# homeboard29.net
KiCad netlist of a schematic drawn in EAGLE
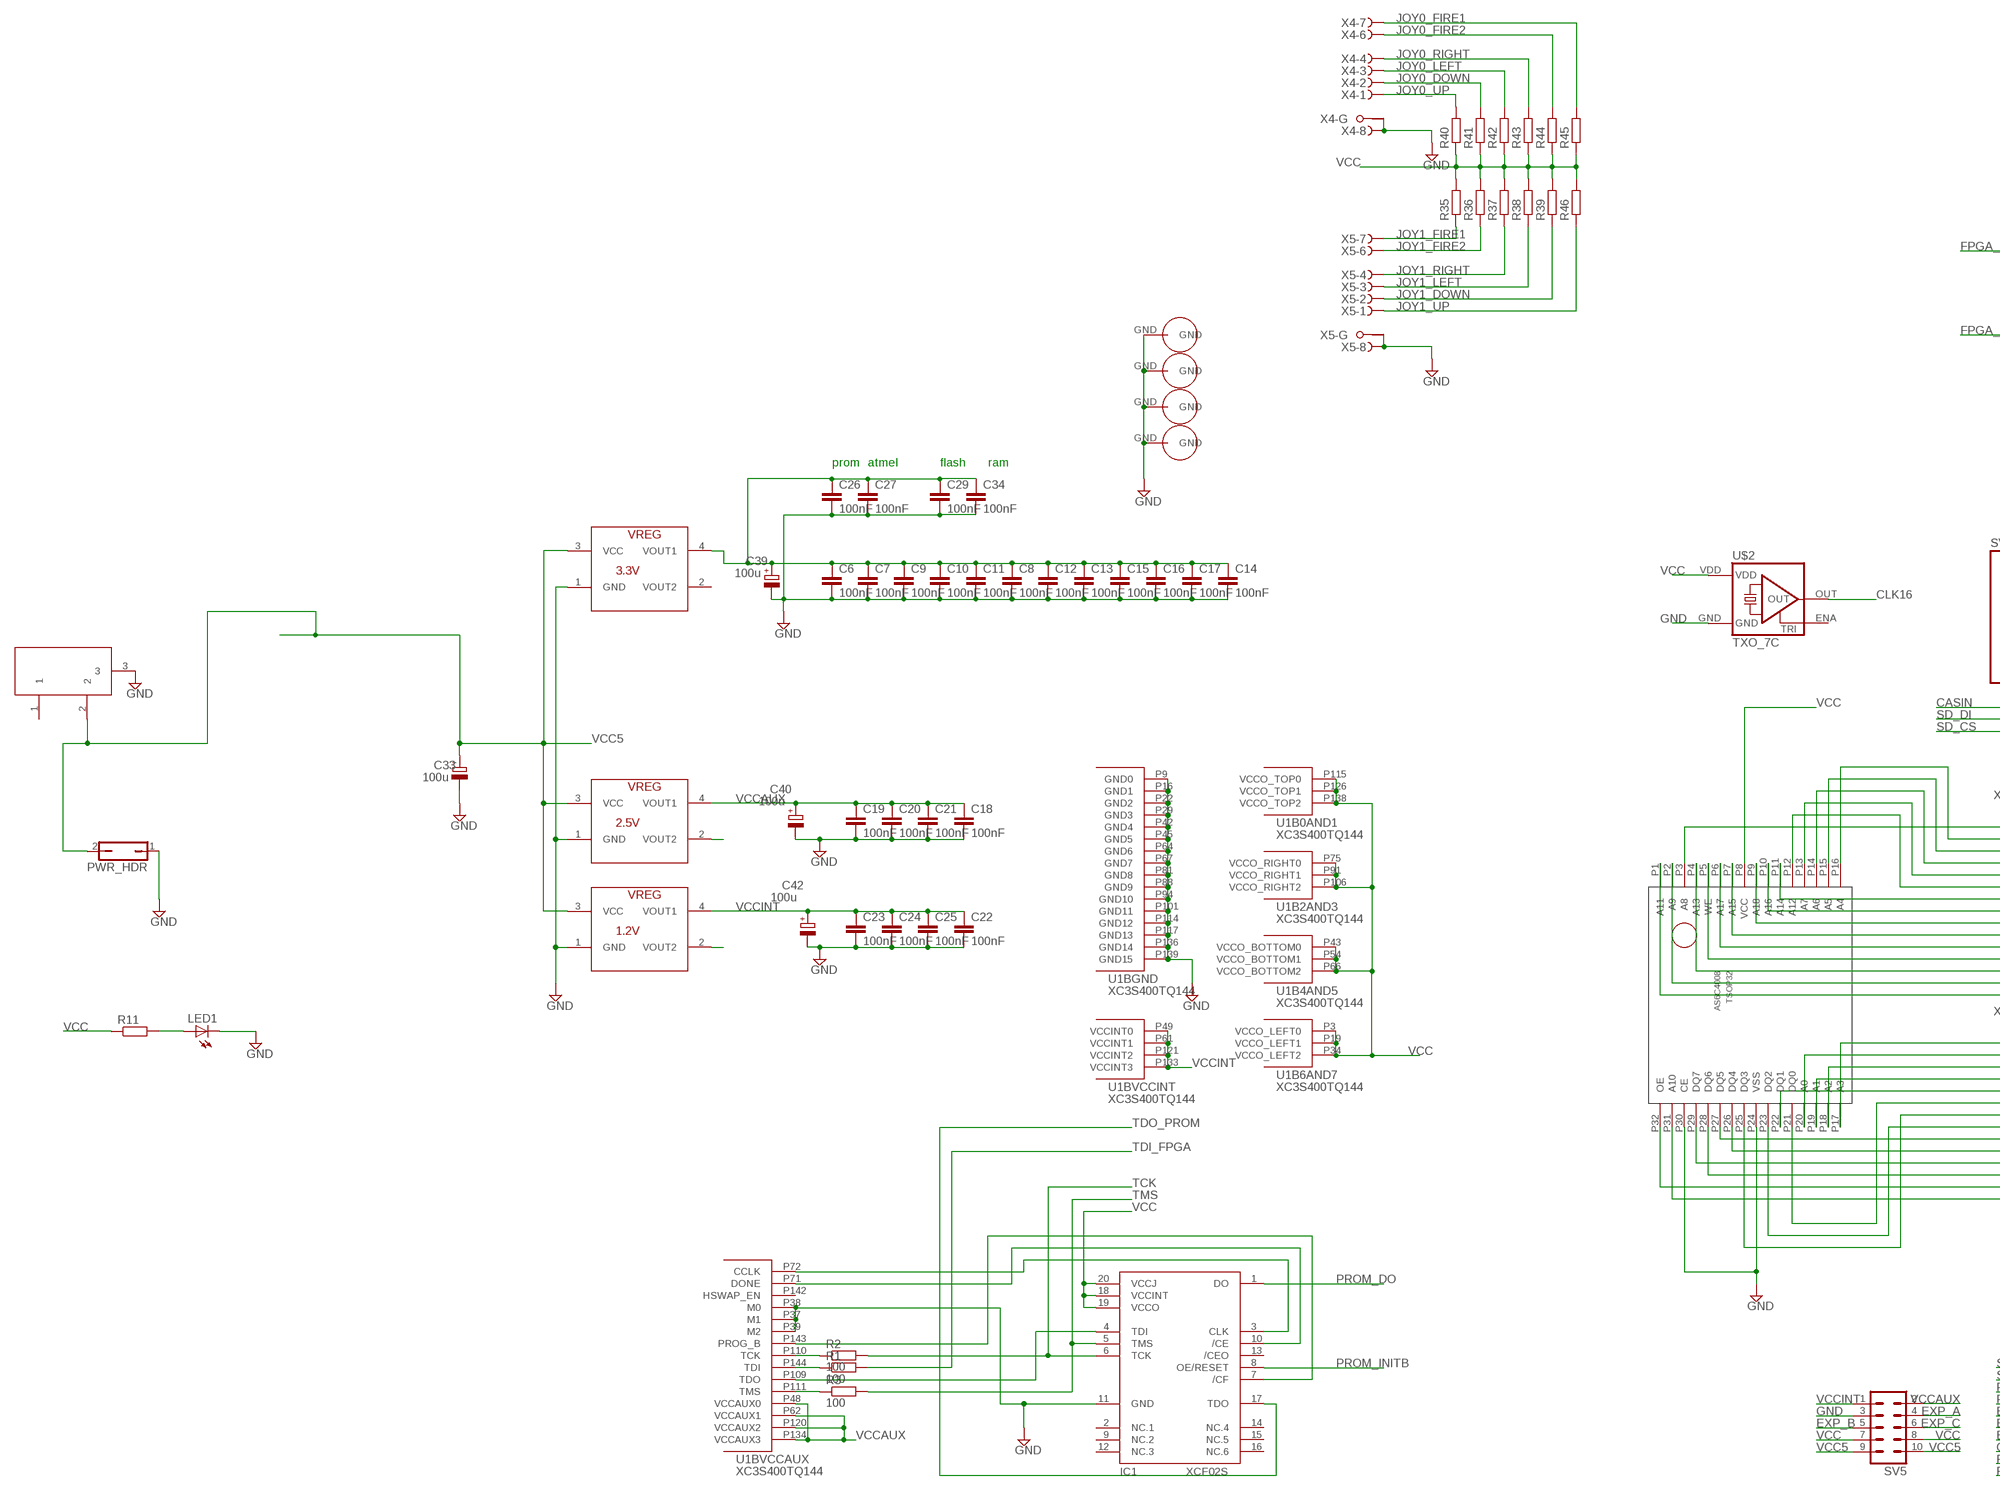
[diagram p0: schematic, sheet 1, part 1 of 3]
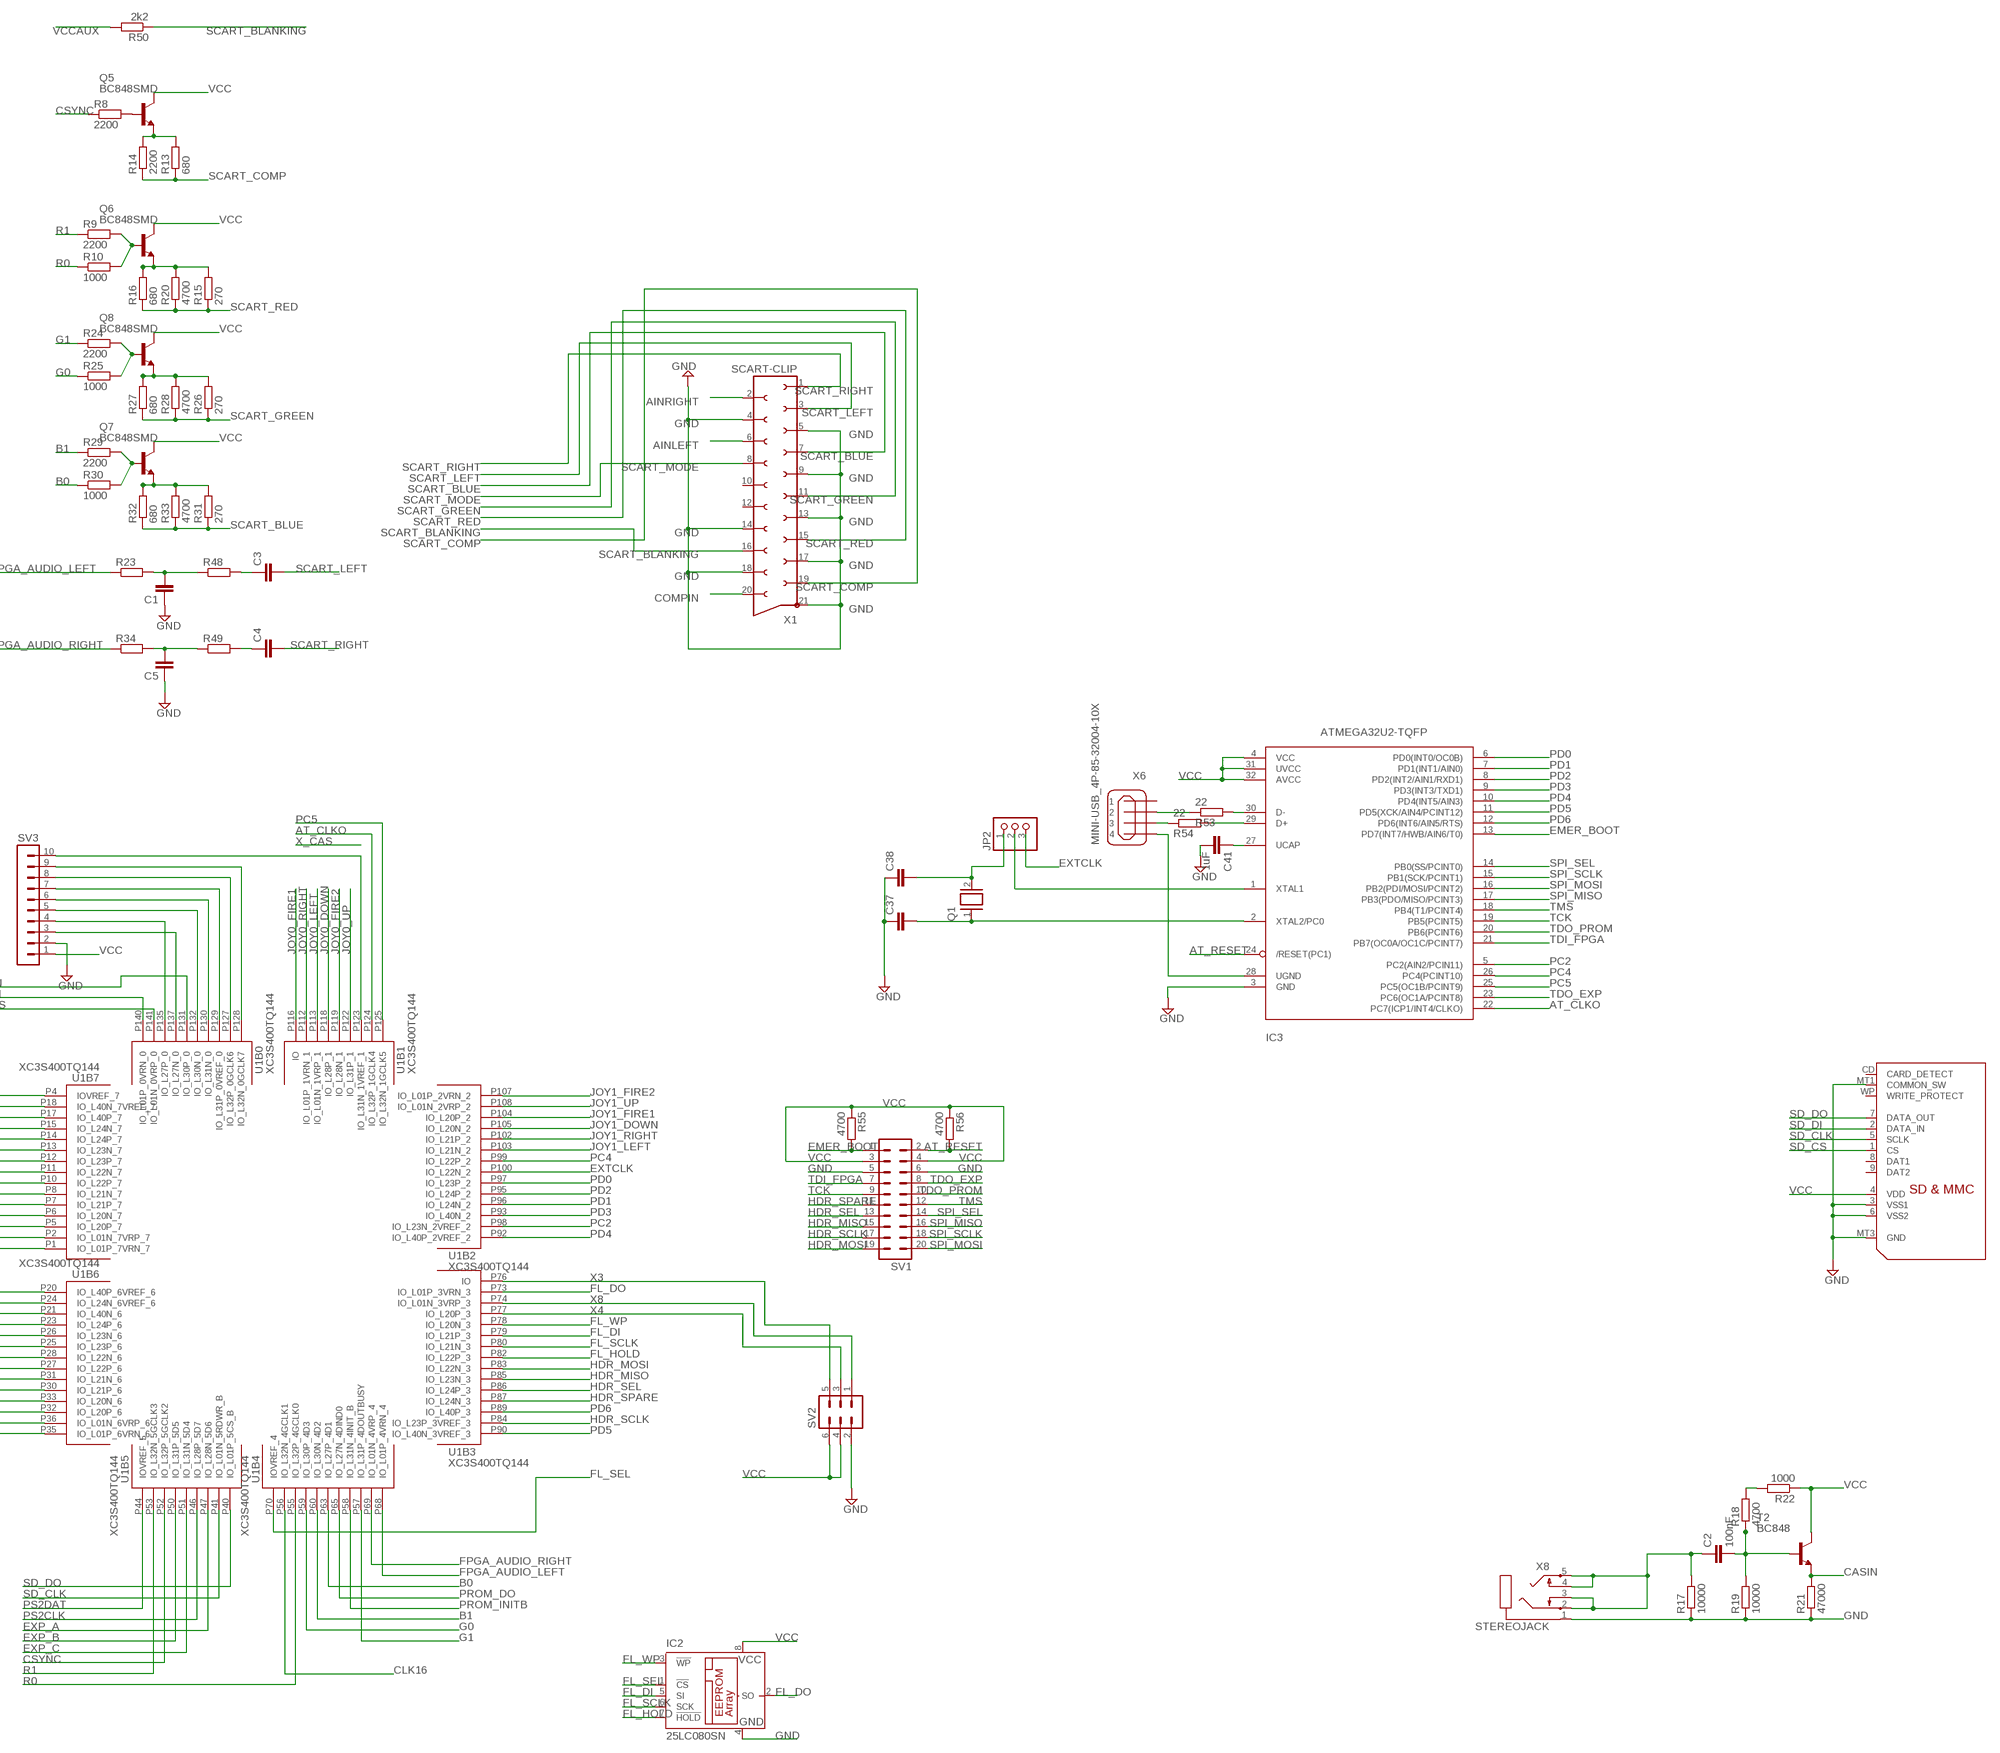
[diagram p1: schematic, sheet 1, part 2 of 3]
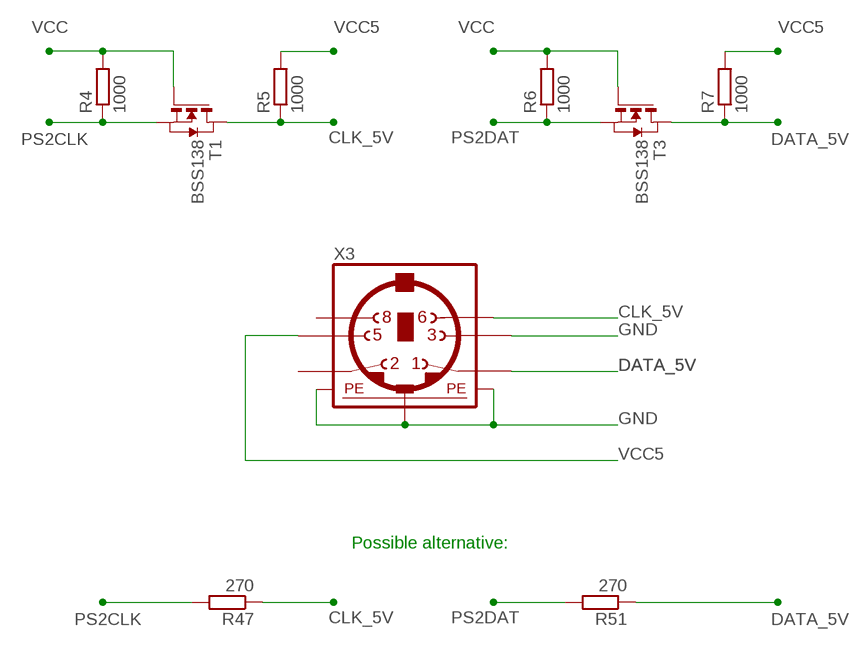
[diagram p2: schematic, sheet 1, part 3 of 3]

(export (version "E")
  (design (tool "Eeschema 10.0.6"))
  (components
    (comp (ref "C1")
      (value "C-EUC0603")
      (footprint "eagle-import:C0603")
      (libsource (lib "eagle-import") (part "resistor_C-EUC0603"))
    )
    (comp (ref "C2")
      (value "100nF")
      (footprint "eagle-import:C0603")
      (libsource (lib "eagle-import") (part "resistor_C-EUC0603"))
    )
    (comp (ref "C3")
      (value "C-EUC0603")
      (footprint "eagle-import:C0603")
      (libsource (lib "eagle-import") (part "resistor_C-EUC0603"))
    )
    (comp (ref "C4")
      (value "C-EUC0603")
      (footprint "eagle-import:C0603")
      (libsource (lib "eagle-import") (part "resistor_C-EUC0603"))
    )
    (comp (ref "C5")
      (value "C-EUC0603")
      (footprint "eagle-import:C0603")
      (libsource (lib "eagle-import") (part "resistor_C-EUC0603"))
    )
    (comp (ref "C6")
      (value "100nF")
      (footprint "eagle-import:C0603")
      (libsource (lib "eagle-import") (part "C-EUC0603"))
    )
    (comp (ref "C7")
      (value "100nF")
      (footprint "eagle-import:C0603")
      (libsource (lib "eagle-import") (part "C-EUC0603"))
    )
    (comp (ref "C8")
      (value "100nF")
      (footprint "eagle-import:C0603")
      (libsource (lib "eagle-import") (part "C-EUC0603"))
    )
    (comp (ref "C9")
      (value "100nF")
      (footprint "eagle-import:C0603")
      (libsource (lib "eagle-import") (part "C-EUC0603"))
    )
    (comp (ref "C10")
      (value "100nF")
      (footprint "eagle-import:C0603")
      (libsource (lib "eagle-import") (part "C-EUC0603"))
    )
    (comp (ref "C11")
      (value "100nF")
      (footprint "eagle-import:C0603")
      (libsource (lib "eagle-import") (part "C-EUC0603"))
    )
    (comp (ref "C12")
      (value "100nF")
      (footprint "eagle-import:C0603")
      (libsource (lib "eagle-import") (part "C-EUC0603"))
    )
    (comp (ref "C13")
      (value "100nF")
      (footprint "eagle-import:C0603")
      (libsource (lib "eagle-import") (part "C-EUC0603"))
    )
    (comp (ref "C14")
      (value "100nF")
      (footprint "eagle-import:C0603")
      (libsource (lib "eagle-import") (part "C-EUC0603"))
    )
    (comp (ref "C15")
      (value "100nF")
      (footprint "eagle-import:C0603")
      (libsource (lib "eagle-import") (part "C-EUC0603"))
    )
    (comp (ref "C16")
      (value "100nF")
      (footprint "eagle-import:C0603")
      (libsource (lib "eagle-import") (part "C-EUC0603"))
    )
    (comp (ref "C17")
      (value "100nF")
      (footprint "eagle-import:C0603")
      (libsource (lib "eagle-import") (part "C-EUC0603"))
    )
    (comp (ref "C18")
      (value "100nF")
      (footprint "eagle-import:C0603")
      (libsource (lib "eagle-import") (part "C-EUC0603"))
    )
    (comp (ref "C19")
      (value "100nF")
      (footprint "eagle-import:C0603")
      (libsource (lib "eagle-import") (part "C-EUC0603"))
    )
    (comp (ref "C20")
      (value "100nF")
      (footprint "eagle-import:C0603")
      (libsource (lib "eagle-import") (part "C-EUC0603"))
    )
    (comp (ref "C21")
      (value "100nF")
      (footprint "eagle-import:C0603")
      (libsource (lib "eagle-import") (part "C-EUC0603"))
    )
    (comp (ref "C22")
      (value "100nF")
      (footprint "eagle-import:C0603")
      (libsource (lib "eagle-import") (part "C-EUC0603"))
    )
    (comp (ref "C23")
      (value "100nF")
      (footprint "eagle-import:C0603")
      (libsource (lib "eagle-import") (part "C-EUC0603"))
    )
    (comp (ref "C24")
      (value "100nF")
      (footprint "eagle-import:C0603")
      (libsource (lib "eagle-import") (part "C-EUC0603"))
    )
    (comp (ref "C25")
      (value "100nF")
      (footprint "eagle-import:C0603")
      (libsource (lib "eagle-import") (part "C-EUC0603"))
    )
    (comp (ref "C26")
      (value "100nF")
      (footprint "eagle-import:C0603")
      (libsource (lib "eagle-import") (part "C-EUC0603"))
    )
    (comp (ref "C27")
      (value "100nF")
      (footprint "eagle-import:C0603")
      (libsource (lib "eagle-import") (part "C-EUC0603"))
    )
    (comp (ref "C29")
      (value "100nF")
      (footprint "eagle-import:C0603")
      (libsource (lib "eagle-import") (part "C-EUC0603"))
    )
    (comp (ref "C33")
      (value "100u")
      (footprint "eagle-import:PANASONIC_D")
      (libsource (lib "eagle-import") (part "CPOL-EUD"))
    )
    (comp (ref "C34")
      (value "100nF")
      (footprint "eagle-import:C0603")
      (libsource (lib "eagle-import") (part "C-EUC0603"))
    )
    (comp (ref "C37")
      (value "C-EUC0805")
      (footprint "eagle-import:C0805")
      (libsource (lib "eagle-import") (part "C-EUC0805"))
    )
    (comp (ref "C38")
      (value "C-EUC0805")
      (footprint "eagle-import:C0805")
      (libsource (lib "eagle-import") (part "C-EUC0805"))
    )
    (comp (ref "C39")
      (value "100u")
      (footprint "eagle-import:PANASONIC_D")
      (libsource (lib "eagle-import") (part "CPOL-EUD"))
    )
    (comp (ref "C40")
      (value "100u")
      (footprint "eagle-import:PANASONIC_D")
      (libsource (lib "eagle-import") (part "CPOL-EUD"))
    )
    (comp (ref "C41")
      (value "1uF")
      (footprint "eagle-import:C0805")
      (libsource (lib "eagle-import") (part "C-EUC0805"))
    )
    (comp (ref "C42")
      (value "100u")
      (footprint "eagle-import:PANASONIC_D")
      (libsource (lib "eagle-import") (part "CPOL-EUD"))
    )
    (comp (ref "IC1")
      (value "XCF02S")
      (footprint "eagle-import:VO20")
      (libsource (lib "eagle-import") (part "XCF02S"))
    )
    (comp (ref "IC2")
      (value "25LC080SN")
      (footprint "eagle-import:SO-08")
      (fields (field (name "MF") "MICROCHIP") (field (name "MPN") "25LC080/SN"))
      (libsource (lib "eagle-import") (part "25SNLC080"))
    )
    (comp (ref "IC3")
      (value "ATMEGA32U2-TQFP")
      (footprint "eagle-import:TQFP32-08")
      (libsource (lib "eagle-import") (part "ATMEGA32U2-TQFP"))
    )
    (comp (ref "JP2")
      (value "PINHD-1X3")
      (footprint "eagle-import:1X03")
      (libsource (lib "eagle-import") (part "PINHD-1X3"))
    )
    (comp (ref "LED1")
      (value "LEDCHIPLED_0805")
      (footprint "eagle-import:CHIPLED_0805")
      (libsource (lib "eagle-import") (part "LEDCHIPLED_0805"))
    )
    (comp (ref "PWR_HDR")
      (value "JP1Q")
      (footprint "eagle-import:JP1")
      (libsource (lib "eagle-import") (part "JP1Q"))
    )
    (comp (ref "Q1")
      (value "XTAL/S")
      (footprint "eagle-import:QS")
      (libsource (lib "eagle-import") (part "XTAL/S"))
    )
    (comp (ref "Q5")
      (value "BC848SMD")
      (footprint "eagle-import:SOT23")
      (libsource (lib "eagle-import") (part "BC848SMD"))
    )
    (comp (ref "Q6")
      (value "BC848SMD")
      (footprint "eagle-import:SOT23")
      (libsource (lib "eagle-import") (part "BC848SMD"))
    )
    (comp (ref "Q7")
      (value "BC848SMD")
      (footprint "eagle-import:SOT23")
      (libsource (lib "eagle-import") (part "BC848SMD"))
    )
    (comp (ref "Q8")
      (value "BC848SMD")
      (footprint "eagle-import:SOT23")
      (libsource (lib "eagle-import") (part "BC848SMD"))
    )
    (comp (ref "R1")
      (value "100")
      (footprint "eagle-import:R0805")
      (libsource (lib "eagle-import") (part "R-EU_R0805"))
    )
    (comp (ref "R2")
      (value "100")
      (footprint "eagle-import:R0805")
      (libsource (lib "eagle-import") (part "R-EU_R0805"))
    )
    (comp (ref "R3")
      (value "100")
      (footprint "eagle-import:R0805")
      (libsource (lib "eagle-import") (part "R-EU_R0805"))
    )
    (comp (ref "R4")
      (value "1000")
      (footprint "eagle-import:R0805")
      (libsource (lib "eagle-import") (part "R-EU_R0805"))
    )
    (comp (ref "R5")
      (value "1000")
      (footprint "eagle-import:R0805")
      (libsource (lib "eagle-import") (part "R-EU_R0805"))
    )
    (comp (ref "R6")
      (value "1000")
      (footprint "eagle-import:R0805")
      (libsource (lib "eagle-import") (part "R-EU_R0805"))
    )
    (comp (ref "R7")
      (value "1000")
      (footprint "eagle-import:R0805")
      (libsource (lib "eagle-import") (part "R-EU_R0805"))
    )
    (comp (ref "R8")
      (value "2200")
      (footprint "eagle-import:R0805")
      (libsource (lib "eagle-import") (part "R-EU_R0805"))
    )
    (comp (ref "R9")
      (value "2200")
      (footprint "eagle-import:R0805")
      (libsource (lib "eagle-import") (part "R-EU_R0805"))
    )
    (comp (ref "R10")
      (value "1000")
      (footprint "eagle-import:R0805")
      (libsource (lib "eagle-import") (part "R-EU_R0805"))
    )
    (comp (ref "R11")
      (value "R-EU_M0805")
      (footprint "eagle-import:M0805")
      (libsource (lib "eagle-import") (part "resistor_R-EU_M0805"))
    )
    (comp (ref "R13")
      (value "680")
      (footprint "eagle-import:R0805")
      (libsource (lib "eagle-import") (part "R-EU_R0805"))
    )
    (comp (ref "R14")
      (value "2200")
      (footprint "eagle-import:R0805")
      (libsource (lib "eagle-import") (part "R-EU_R0805"))
    )
    (comp (ref "R15")
      (value "270")
      (footprint "eagle-import:R0805")
      (libsource (lib "eagle-import") (part "R-EU_R0805"))
    )
    (comp (ref "R16")
      (value "680")
      (footprint "eagle-import:R0805")
      (libsource (lib "eagle-import") (part "R-EU_R0805"))
    )
    (comp (ref "R17")
      (value "10000")
      (footprint "eagle-import:R0805")
      (libsource (lib "eagle-import") (part "R-EU_R0805"))
    )
    (comp (ref "R18")
      (value "4700")
      (footprint "eagle-import:R0805")
      (libsource (lib "eagle-import") (part "R-EU_R0805"))
    )
    (comp (ref "R19")
      (value "10000")
      (footprint "eagle-import:R0805")
      (libsource (lib "eagle-import") (part "R-EU_R0805"))
    )
    (comp (ref "R20")
      (value "4700")
      (footprint "eagle-import:R0805")
      (libsource (lib "eagle-import") (part "R-EU_R0805"))
    )
    (comp (ref "R21")
      (value "47000")
      (footprint "eagle-import:R0805")
      (libsource (lib "eagle-import") (part "R-EU_R0805"))
    )
    (comp (ref "R22")
      (value "1000")
      (footprint "eagle-import:R0805")
      (libsource (lib "eagle-import") (part "R-EU_R0805"))
    )
    (comp (ref "R23")
      (value "R-EU_M0805")
      (footprint "eagle-import:M0805")
      (libsource (lib "eagle-import") (part "resistor_R-EU_M0805"))
    )
    (comp (ref "R24")
      (value "2200")
      (footprint "eagle-import:R0805")
      (libsource (lib "eagle-import") (part "R-EU_R0805"))
    )
    (comp (ref "R25")
      (value "1000")
      (footprint "eagle-import:R0805")
      (libsource (lib "eagle-import") (part "R-EU_R0805"))
    )
    (comp (ref "R26")
      (value "270")
      (footprint "eagle-import:R0805")
      (libsource (lib "eagle-import") (part "R-EU_R0805"))
    )
    (comp (ref "R27")
      (value "680")
      (footprint "eagle-import:R0805")
      (libsource (lib "eagle-import") (part "R-EU_R0805"))
    )
    (comp (ref "R28")
      (value "4700")
      (footprint "eagle-import:R0805")
      (libsource (lib "eagle-import") (part "R-EU_R0805"))
    )
    (comp (ref "R29")
      (value "2200")
      (footprint "eagle-import:R0805")
      (libsource (lib "eagle-import") (part "R-EU_R0805"))
    )
    (comp (ref "R30")
      (value "1000")
      (footprint "eagle-import:R0805")
      (libsource (lib "eagle-import") (part "R-EU_R0805"))
    )
    (comp (ref "R31")
      (value "270")
      (footprint "eagle-import:R0805")
      (libsource (lib "eagle-import") (part "R-EU_R0805"))
    )
    (comp (ref "R32")
      (value "680")
      (footprint "eagle-import:R0805")
      (libsource (lib "eagle-import") (part "R-EU_R0805"))
    )
    (comp (ref "R33")
      (value "4700")
      (footprint "eagle-import:R0805")
      (libsource (lib "eagle-import") (part "R-EU_R0805"))
    )
    (comp (ref "R34")
      (value "R-EU_M0805")
      (footprint "eagle-import:M0805")
      (libsource (lib "eagle-import") (part "resistor_R-EU_M0805"))
    )
    (comp (ref "R35")
      (value "R-EU_M0805")
      (footprint "eagle-import:M0805")
      (libsource (lib "eagle-import") (part "resistor_R-EU_M0805"))
    )
    (comp (ref "R36")
      (value "R-EU_M0805")
      (footprint "eagle-import:M0805")
      (libsource (lib "eagle-import") (part "resistor_R-EU_M0805"))
    )
    (comp (ref "R37")
      (value "R-EU_M0805")
      (footprint "eagle-import:M0805")
      (libsource (lib "eagle-import") (part "resistor_R-EU_M0805"))
    )
    (comp (ref "R38")
      (value "R-EU_M0805")
      (footprint "eagle-import:M0805")
      (libsource (lib "eagle-import") (part "resistor_R-EU_M0805"))
    )
    (comp (ref "R39")
      (value "R-EU_M0805")
      (footprint "eagle-import:M0805")
      (libsource (lib "eagle-import") (part "resistor_R-EU_M0805"))
    )
    (comp (ref "R40")
      (value "R-EU_M0805")
      (footprint "eagle-import:M0805")
      (libsource (lib "eagle-import") (part "resistor_R-EU_M0805"))
    )
    (comp (ref "R41")
      (value "R-EU_M0805")
      (footprint "eagle-import:M0805")
      (libsource (lib "eagle-import") (part "resistor_R-EU_M0805"))
    )
    (comp (ref "R42")
      (value "R-EU_M0805")
      (footprint "eagle-import:M0805")
      (libsource (lib "eagle-import") (part "resistor_R-EU_M0805"))
    )
    (comp (ref "R43")
      (value "R-EU_M0805")
      (footprint "eagle-import:M0805")
      (libsource (lib "eagle-import") (part "resistor_R-EU_M0805"))
    )
    (comp (ref "R44")
      (value "R-EU_M0805")
      (footprint "eagle-import:M0805")
      (libsource (lib "eagle-import") (part "resistor_R-EU_M0805"))
    )
    (comp (ref "R45")
      (value "R-EU_M0805")
      (footprint "eagle-import:M0805")
      (libsource (lib "eagle-import") (part "resistor_R-EU_M0805"))
    )
    (comp (ref "R46")
      (value "R-EU_M0805")
      (footprint "eagle-import:M0805")
      (libsource (lib "eagle-import") (part "resistor_R-EU_M0805"))
    )
    (comp (ref "R47")
      (value "270")
      (footprint "eagle-import:R0805")
      (libsource (lib "eagle-import") (part "R-EU_R0805"))
    )
    (comp (ref "R48")
      (value "R-EU_M0805")
      (footprint "eagle-import:M0805")
      (libsource (lib "eagle-import") (part "resistor_R-EU_M0805"))
    )
    (comp (ref "R49")
      (value "R-EU_M0805")
      (footprint "eagle-import:M0805")
      (libsource (lib "eagle-import") (part "resistor_R-EU_M0805"))
    )
    (comp (ref "R50")
      (value "2k2")
      (footprint "eagle-import:M0805")
      (libsource (lib "eagle-import") (part "resistor_R-EU_M0805"))
    )
    (comp (ref "R51")
      (value "270")
      (footprint "eagle-import:R0805")
      (libsource (lib "eagle-import") (part "R-EU_R0805"))
    )
    (comp (ref "R53")
      (value "22")
      (footprint "eagle-import:R0805")
      (libsource (lib "eagle-import") (part "R-EU_R0805"))
    )
    (comp (ref "R54")
      (value "22")
      (footprint "eagle-import:R0805")
      (libsource (lib "eagle-import") (part "R-EU_R0805"))
    )
    (comp (ref "R55")
      (value "4700")
      (footprint "eagle-import:R0805")
      (libsource (lib "eagle-import") (part "R-EU_R0805"))
    )
    (comp (ref "R56")
      (value "4700")
      (footprint "eagle-import:R0805")
      (libsource (lib "eagle-import") (part "R-EU_R0805"))
    )
    (comp (ref "REG1.2")
      (value "1.2V")
      (footprint "eagle-import:SOT223")
      (libsource (lib "eagle-import") (part "NX1117"))
    )
    (comp (ref "REG2.5")
      (value "2.5V")
      (footprint "eagle-import:SOT223")
      (libsource (lib "eagle-import") (part "NX1117"))
    )
    (comp (ref "SV1")
      (value "MA10-2")
      (footprint "eagle-import:MA10-2")
      (fields (field (name "OC_FARNELL") "unknown") (field (name "OC_NEWARK") "unknown"))
      (libsource (lib "eagle-import") (part "MA10-2"))
    )
    (comp (ref "SV2")
      (value "MA03-2")
      (footprint "eagle-import:MA03-2")
      (libsource (lib "eagle-import") (part "MA03-2"))
    )
    (comp (ref "SV3")
      (value "MA10-1")
      (footprint "eagle-import:MA10-1")
      (libsource (lib "eagle-import") (part "MA10-1"))
    )
    (comp (ref "SV5")
      (value "MA05-2")
      (footprint "eagle-import:MA05-2")
      (libsource (lib "eagle-import") (part "MA05-2"))
    )
    (comp (ref "T1")
      (value "BSS138")
      (footprint "eagle-import:SOT-23")
      (libsource (lib "eagle-import") (part "NMOSSOT23"))
    )
    (comp (ref "T2")
      (value "BC848")
      (footprint "eagle-import:SOT23")
      (libsource (lib "eagle-import") (part "BC848"))
    )
    (comp (ref "T3")
      (value "BSS138")
      (footprint "eagle-import:SOT-23")
      (libsource (lib "eagle-import") (part "NMOSSOT23"))
    )
    (comp (ref "U$1")
      (value "GNDHOLE")
      (footprint "eagle-import:GNDHOLE")
      (libsource (lib "eagle-import") (part "GNDHOLE"))
    )
    (comp (ref "U$2")
      (value "TXO_7C")
      (footprint "eagle-import:OSC_7C")
      (libsource (lib "eagle-import") (part "TXO_7C"))
    )
    (comp (ref "U$3")
      (value "SDMMCNOHOLE")
      (footprint "eagle-import:SDCARD-NOHOLE")
      (libsource (lib "eagle-import") (part "SDMMCNOHOLE"))
    )
    (comp (ref "U$4")
      (value "3.3V")
      (footprint "eagle-import:SOT223")
      (libsource (lib "eagle-import") (part "NX1117"))
    )
    (comp (ref "U$6")
      (value "AS6C4008")
      (footprint "eagle-import:TSOP32")
      (libsource (lib "eagle-import") (part "AS6C4008"))
    )
    (comp (ref "U$7")
      (value "GNDHOLE")
      (footprint "eagle-import:GNDHOLE")
      (libsource (lib "eagle-import") (part "GNDHOLE"))
    )
    (comp (ref "U$8")
      (value "GNDHOLE")
      (footprint "eagle-import:GNDHOLE")
      (libsource (lib "eagle-import") (part "GNDHOLE"))
    )
    (comp (ref "U$9")
      (value "GNDHOLE")
      (footprint "eagle-import:GNDHOLE")
      (libsource (lib "eagle-import") (part "GNDHOLE"))
    )
    (comp (ref "U1")
      (value "XC3S400TQ144")
      (footprint "eagle-import:TQ144")
      (libsource (lib "eagle-import") (part "XC3S400TQ144"))
    )
    (comp (ref "X1")
      (value "SCART-CLIP")
      (footprint "eagle-import:SCART-CLIP")
      (libsource (lib "eagle-import") (part "SCART-CLIP"))
    )
    (comp (ref "X3")
      (value "MINI_DIN_6")
      (footprint "eagle-import:M_DIN6")
      (libsource (lib "eagle-import") (part "MINI_DIN_6"))
    )
    (comp (ref "X4")
      (value "F09HPS")
      (footprint "eagle-import:F09HP")
      (libsource (lib "eagle-import") (part "F09HPS"))
    )
    (comp (ref "X5")
      (value "F09HPS")
      (footprint "eagle-import:F09HP")
      (libsource (lib "eagle-import") (part "F09HPS"))
    )
    (comp (ref "X6")
      (value "MINI-USB_4P-85-32004-10X")
      (footprint "eagle-import:85-32004-10X")
      (libsource (lib "eagle-import") (part "MINI-USB_4P-85-32004-10X"))
    )
    (comp (ref "X7")
      (value "DC21MMX")
      (footprint "eagle-import:DC-21MM")
      (libsource (lib "eagle-import") (part "DC21MMX"))
    )
    (comp (ref "X8")
      (value "STEREOJACK")
      (footprint "eagle-import:20-0137")
      (libsource (lib "eagle-import") (part "STEREOJACK"))
    )
  )
  (nets
    (net (code "1") (name "/1") (class "Default")
      (node (ref "X7") (pin "1") (pinfunction "1_1") (pintype "power_in"))
    )
    (net (code "2") (name "/AINLEFT") (class "Default")
      (node (ref "X1") (pin "6") (pinfunction "6_6") (pintype "passive"))
    )
    (net (code "3") (name "/AINRIGHT") (class "Default")
      (node (ref "X1") (pin "2") (pinfunction "2_2") (pintype "passive"))
    )
    (net (code "4") (name "/AT_CLKO") (class "Default")
      (node (ref "IC3") (pin "22") (pinfunction "PC7(ICP1/INT4/CLKO)_22") (pintype "bidirectional"))
      (node (ref "U1") (pin "P124") (pinfunction "IO_L32P_1GCLK4_P124") (pintype "bidirectional"))
    )
    (net (code "5") (name "/AT_RESET") (class "Default")
      (node (ref "IC3") (pin "24") (pinfunction "/RESET(PC1)_24") (pintype "bidirectional"))
      (node (ref "R56") (pin "2") (pinfunction "2_2") (pintype "passive"))
      (node (ref "SV1") (pin "2") (pinfunction "2_2") (pintype "passive"))
    )
    (net (code "6") (name "/B0") (class "Default")
      (node (ref "R30") (pin "1") (pinfunction "1_1") (pintype "passive"))
      (node (ref "U1") (pin "P63") (pinfunction "IO_L27P_4D1_P63") (pintype "bidirectional"))
    )
    (net (code "7") (name "/B1") (class "Default")
      (node (ref "R29") (pin "1") (pinfunction "1_1") (pintype "passive"))
      (node (ref "U1") (pin "P60") (pinfunction "IO_L30N_4D2_P60") (pintype "bidirectional"))
    )
    (net (code "8") (name "/CASIN") (class "Default")
      (node (ref "R21") (pin "2") (pinfunction "2_2") (pintype "passive"))
      (node (ref "T2") (pin "2") (pinfunction "E_2") (pintype "passive"))
      (node (ref "U1") (pin "P131") (pinfunction "IO_L30P_0_P131") (pintype "bidirectional"))
    )
    (net (code "9") (name "/CLK16") (class "Default")
      (node (ref "U$2") (pin "OUT") (pinfunction "OUT_OUT") (pintype "output"))
      (node (ref "U1") (pin "P56") (pinfunction "IO_L32N_4GCLK1_P56") (pintype "bidirectional"))
    )
    (net (code "10") (name "/CLK_5V") (class "Default")
      (node (ref "R47") (pin "1") (pinfunction "1_1") (pintype "passive"))
      (node (ref "R5") (pin "1") (pinfunction "1_1") (pintype "passive"))
      (node (ref "T1") (pin "1") (pinfunction "D_1") (pintype "passive"))
      (node (ref "X3") (pin "6") (pinfunction "6_6") (pintype "passive"))
    )
    (net (code "11") (name "/COMPIN") (class "Default")
      (node (ref "X1") (pin "20") (pinfunction "20_20") (pintype "passive"))
    )
    (net (code "12") (name "/CSYNC") (class "Default")
      (node (ref "R8") (pin "1") (pinfunction "1_1") (pintype "passive"))
      (node (ref "U1") (pin "P52") (pinfunction "IO_L32P_5GCLK2_P52") (pintype "bidirectional"))
    )
    (net (code "13") (name "/DATA_5V") (class "Default")
      (node (ref "R51") (pin "1") (pinfunction "1_1") (pintype "passive"))
      (node (ref "R7") (pin "1") (pinfunction "1_1") (pintype "passive"))
      (node (ref "T3") (pin "1") (pinfunction "D_1") (pintype "passive"))
      (node (ref "X3") (pin "1") (pinfunction "1_1") (pintype "passive"))
    )
    (net (code "14") (name "/EMER_BOOT") (class "Default")
      (node (ref "IC3") (pin "13") (pinfunction "PD7(INT7/HWB/AIN6/T0)_13") (pintype "bidirectional"))
      (node (ref "R55") (pin "2") (pinfunction "2_2") (pintype "passive"))
      (node (ref "SV1") (pin "1") (pinfunction "1_1") (pintype "passive"))
    )
    (net (code "15") (name "/EXP_A") (class "Default")
      (node (ref "SV5") (pin "4") (pinfunction "4_4") (pintype "passive"))
      (node (ref "U1") (pin "P47") (pinfunction "IO_L28N_5D6_P47") (pintype "bidirectional"))
    )
    (net (code "16") (name "/EXP_B") (class "Default")
      (node (ref "SV5") (pin "5") (pinfunction "5_5") (pintype "passive"))
      (node (ref "U1") (pin "P50") (pinfunction "IO_L31P_5D5_P50") (pintype "bidirectional"))
    )
    (net (code "17") (name "/EXP_C") (class "Default")
      (node (ref "SV5") (pin "6") (pinfunction "6_6") (pintype "passive"))
      (node (ref "U1") (pin "P51") (pinfunction "IO_L31N_5D4_P51") (pintype "bidirectional"))
    )
    (net (code "18") (name "/EXTCLK") (class "Default")
      (node (ref "JP2") (pin "3") (pinfunction "3_3") (pintype "passive"))
      (node (ref "U1") (pin "P100") (pinfunction "IO_L22N_2_P100") (pintype "bidirectional"))
    )
    (net (code "19") (name "/FL_DI") (class "Default")
      (node (ref "IC2") (pin "5") (pinfunction "SI_5") (pintype "input"))
      (node (ref "U1") (pin "P79") (pinfunction "IO_L21P_3_P79") (pintype "bidirectional"))
    )
    (net (code "20") (name "/FL_DO") (class "Default")
      (node (ref "IC2") (pin "2") (pinfunction "SO_2") (pintype "bidirectional"))
      (node (ref "U1") (pin "P73") (pinfunction "IO_L01P_3VRN_3_P73") (pintype "bidirectional"))
    )
    (net (code "21") (name "/FL_HOLD") (class "Default")
      (node (ref "IC2") (pin "7") (pinfunction "~{HOLD}_7") (pintype "input"))
      (node (ref "U1") (pin "P82") (pinfunction "IO_L22P_3_P82") (pintype "bidirectional"))
    )
    (net (code "22") (name "/FL_SCLK") (class "Default")
      (node (ref "IC2") (pin "6") (pinfunction "SCK_6") (pintype "input"))
      (node (ref "U1") (pin "P80") (pinfunction "IO_L21N_3_P80") (pintype "bidirectional"))
    )
    (net (code "23") (name "/FL_SEL") (class "Default")
      (node (ref "IC2") (pin "1") (pinfunction "~{CS}_1") (pintype "input"))
      (node (ref "U1") (pin "P70") (pinfunction "IOVREF_4_P70") (pintype "bidirectional"))
    )
    (net (code "24") (name "/FL_WP") (class "Default")
      (node (ref "IC2") (pin "3") (pinfunction "~{WP}_3") (pintype "input"))
      (node (ref "U1") (pin "P78") (pinfunction "IO_L20N_3_P78") (pintype "bidirectional"))
    )
    (net (code "25") (name "/FPGA_AUDIO_LEFT") (class "Default")
      (node (ref "R23") (pin "1") (pinfunction "1_1") (pintype "passive"))
      (node (ref "U1") (pin "P68") (pinfunction "IO_L01P_4VRN_4_P68") (pintype "bidirectional"))
    )
    (net (code "26") (name "/FPGA_AUDIO_RIGHT") (class "Default")
      (node (ref "R34") (pin "1") (pinfunction "1_1") (pintype "passive"))
      (node (ref "U1") (pin "P69") (pinfunction "IO_L01N_4VRP_4_P69") (pintype "bidirectional"))
    )
    (net (code "27") (name "/G0") (class "Default")
      (node (ref "R25") (pin "1") (pinfunction "1_1") (pintype "passive"))
      (node (ref "U1") (pin "P59") (pinfunction "IO_L30P_4D3_P59") (pintype "bidirectional"))
    )
    (net (code "28") (name "/G1") (class "Default")
      (node (ref "R24") (pin "1") (pinfunction "1_1") (pintype "passive"))
      (node (ref "U1") (pin "P57") (pinfunction "IO_L31P_4DOUTBUSY_P57") (pintype "bidirectional"))
    )
    (net (code "29") (name "/HDR_MISO") (class "Default")
      (node (ref "SV1") (pin "15") (pinfunction "15_15") (pintype "passive"))
      (node (ref "U1") (pin "P85") (pinfunction "IO_L23N_3_P85") (pintype "bidirectional"))
    )
    (net (code "30") (name "/HDR_MOSI") (class "Default")
      (node (ref "SV1") (pin "19") (pinfunction "19_19") (pintype "passive"))
      (node (ref "U1") (pin "P83") (pinfunction "IO_L22N_3_P83") (pintype "bidirectional"))
    )
    (net (code "31") (name "/HDR_SCLK") (class "Default")
      (node (ref "SV1") (pin "17") (pinfunction "17_17") (pintype "passive"))
      (node (ref "U1") (pin "P84") (pinfunction "IO_L23P_3VREF_3_P84") (pintype "bidirectional"))
    )
    (net (code "32") (name "/HDR_SEL") (class "Default")
      (node (ref "SV1") (pin "13") (pinfunction "13_13") (pintype "passive"))
      (node (ref "U1") (pin "P86") (pinfunction "IO_L24P_3_P86") (pintype "bidirectional"))
    )
    (net (code "33") (name "/HDR_SPARE") (class "Default")
      (node (ref "SV1") (pin "11") (pinfunction "11_11") (pintype "passive"))
      (node (ref "U1") (pin "P87") (pinfunction "IO_L24N_3_P87") (pintype "bidirectional"))
    )
    (net (code "34") (name "/JOY0_DOWN") (class "Default")
      (node (ref "R41") (pin "2") (pinfunction "2_2") (pintype "passive"))
      (node (ref "U1") (pin "P118") (pinfunction "IO_L28P_1_P118") (pintype "bidirectional"))
      (node (ref "X4") (pin "2") (pinfunction "F_2") (pintype "passive"))
    )
    (net (code "35") (name "/JOY0_FIRE1") (class "Default")
      (node (ref "R45") (pin "2") (pinfunction "2_2") (pintype "passive"))
      (node (ref "U1") (pin "P116") (pinfunction "IO_P116") (pintype "bidirectional"))
      (node (ref "X4") (pin "7") (pinfunction "F_7") (pintype "passive"))
    )
    (net (code "36") (name "/JOY0_FIRE2") (class "Default")
      (node (ref "R44") (pin "2") (pinfunction "2_2") (pintype "passive"))
      (node (ref "U1") (pin "P119") (pinfunction "IO_L28N_1_P119") (pintype "bidirectional"))
      (node (ref "X4") (pin "6") (pinfunction "F_6") (pintype "passive"))
    )
    (net (code "37") (name "/JOY0_LEFT") (class "Default")
      (node (ref "R42") (pin "2") (pinfunction "2_2") (pintype "passive"))
      (node (ref "U1") (pin "P113") (pinfunction "IO_L01N_1VRP_1_P113") (pintype "bidirectional"))
      (node (ref "X4") (pin "3") (pinfunction "F_3") (pintype "passive"))
    )
    (net (code "38") (name "/JOY0_RIGHT") (class "Default")
      (node (ref "R43") (pin "2") (pinfunction "2_2") (pintype "passive"))
      (node (ref "U1") (pin "P112") (pinfunction "IO_L01P_1VRN_1_P112") (pintype "bidirectional"))
      (node (ref "X4") (pin "4") (pinfunction "F_4") (pintype "passive"))
    )
    (net (code "39") (name "/JOY0_UP") (class "Default")
      (node (ref "R40") (pin "2") (pinfunction "2_2") (pintype "passive"))
      (node (ref "U1") (pin "P122") (pinfunction "IO_L31P_1_P122") (pintype "bidirectional"))
      (node (ref "X4") (pin "1") (pinfunction "F_1") (pintype "passive"))
    )
    (net (code "40") (name "/JOY1_DOWN") (class "Default")
      (node (ref "R39") (pin "1") (pinfunction "1_1") (pintype "passive"))
      (node (ref "U1") (pin "P105") (pinfunction "IO_L20N_2_P105") (pintype "bidirectional"))
      (node (ref "X5") (pin "2") (pinfunction "F_2") (pintype "passive"))
    )
    (net (code "41") (name "/JOY1_FIRE1") (class "Default")
      (node (ref "R35") (pin "1") (pinfunction "1_1") (pintype "passive"))
      (node (ref "U1") (pin "P104") (pinfunction "IO_L20P_2_P104") (pintype "bidirectional"))
      (node (ref "X5") (pin "7") (pinfunction "F_7") (pintype "passive"))
    )
    (net (code "42") (name "/JOY1_FIRE2") (class "Default")
      (node (ref "R36") (pin "1") (pinfunction "1_1") (pintype "passive"))
      (node (ref "U1") (pin "P107") (pinfunction "IO_L01P_2VRN_2_P107") (pintype "bidirectional"))
      (node (ref "X5") (pin "6") (pinfunction "F_6") (pintype "passive"))
    )
    (net (code "43") (name "/JOY1_LEFT") (class "Default")
      (node (ref "R38") (pin "1") (pinfunction "1_1") (pintype "passive"))
      (node (ref "U1") (pin "P103") (pinfunction "IO_L21N_2_P103") (pintype "bidirectional"))
      (node (ref "X5") (pin "3") (pinfunction "F_3") (pintype "passive"))
    )
    (net (code "44") (name "/JOY1_RIGHT") (class "Default")
      (node (ref "R37") (pin "1") (pinfunction "1_1") (pintype "passive"))
      (node (ref "U1") (pin "P102") (pinfunction "IO_L21P_2_P102") (pintype "bidirectional"))
      (node (ref "X5") (pin "4") (pinfunction "F_4") (pintype "passive"))
    )
    (net (code "45") (name "/JOY1_UP") (class "Default")
      (node (ref "R46") (pin "1") (pinfunction "1_1") (pintype "passive"))
      (node (ref "U1") (pin "P108") (pinfunction "IO_L01N_2VRP_2_P108") (pintype "bidirectional"))
      (node (ref "X5") (pin "1") (pinfunction "F_1") (pintype "passive"))
    )
    (net (code "46") (name "/PC2") (class "Default")
      (node (ref "IC3") (pin "5") (pinfunction "PC2(AIN2/PCIN11)_5") (pintype "bidirectional"))
      (node (ref "U1") (pin "P98") (pinfunction "IO_L23N_2VREF_2_P98") (pintype "bidirectional"))
    )
    (net (code "47") (name "/PC4") (class "Default")
      (node (ref "IC3") (pin "26") (pinfunction "PC4(PCINT10)_26") (pintype "bidirectional"))
      (node (ref "U1") (pin "P99") (pinfunction "IO_L22P_2_P99") (pintype "bidirectional"))
    )
    (net (code "48") (name "/PC5") (class "Default")
      (node (ref "IC3") (pin "25") (pinfunction "PC5(OC1B/PCINT9)_25") (pintype "bidirectional"))
      (node (ref "U1") (pin "P125") (pinfunction "IO_L32N_1GCLK5_P125") (pintype "bidirectional"))
    )
    (net (code "49") (name "/PD0") (class "Default")
      (node (ref "IC3") (pin "6") (pinfunction "PD0(INT0/OC0B)_6") (pintype "bidirectional"))
      (node (ref "U1") (pin "P97") (pinfunction "IO_L23P_2_P97") (pintype "bidirectional"))
    )
    (net (code "50") (name "/PD1") (class "Default")
      (node (ref "IC3") (pin "7") (pinfunction "PD1(INT1/AIN0)_7") (pintype "bidirectional"))
      (node (ref "U1") (pin "P96") (pinfunction "IO_L24N_2_P96") (pintype "bidirectional"))
    )
    (net (code "51") (name "/PD2") (class "Default")
      (node (ref "IC3") (pin "8") (pinfunction "PD2(INT2/AIN1/RXD1)_8") (pintype "bidirectional"))
      (node (ref "U1") (pin "P95") (pinfunction "IO_L24P_2_P95") (pintype "bidirectional"))
    )
    (net (code "52") (name "/PD3") (class "Default")
      (node (ref "IC3") (pin "9") (pinfunction "PD3(INT3/TXD1)_9") (pintype "bidirectional"))
      (node (ref "U1") (pin "P93") (pinfunction "IO_L40N_2_P93") (pintype "bidirectional"))
    )
    (net (code "53") (name "/PD4") (class "Default")
      (node (ref "IC3") (pin "10") (pinfunction "PD4(INT5/AIN3)_10") (pintype "bidirectional"))
      (node (ref "U1") (pin "P92") (pinfunction "IO_L40P_2VREF_2_P92") (pintype "bidirectional"))
    )
    (net (code "54") (name "/PD5") (class "Default")
      (node (ref "IC3") (pin "11") (pinfunction "PD5(XCK/AIN4/PCINT12)_11") (pintype "bidirectional"))
      (node (ref "U1") (pin "P90") (pinfunction "IO_L40N_3VREF_3_P90") (pintype "bidirectional"))
    )
    (net (code "55") (name "/PD6") (class "Default")
      (node (ref "IC3") (pin "12") (pinfunction "PD6(INT6/AIN5/RTS)_12") (pintype "bidirectional"))
      (node (ref "U1") (pin "P89") (pinfunction "IO_L40P_3_P89") (pintype "bidirectional"))
    )
    (net (code "56") (name "/PROM_DO") (class "Default")
      (node (ref "IC1") (pin "1") (pinfunction "DO_1") (pintype "bidirectional"))
      (node (ref "U1") (pin "P65") (pinfunction "IO_L27N_4DIND0_P65") (pintype "bidirectional"))
    )
    (net (code "57") (name "/PROM_INITB") (class "Default")
      (node (ref "IC1") (pin "8") (pinfunction "OE/RESET_8") (pintype "bidirectional"))
      (node (ref "U1") (pin "P58") (pinfunction "IO_L31N_4INIT_B_P58") (pintype "bidirectional"))
    )
    (net (code "58") (name "/PS2CLK") (class "Default")
      (node (ref "R4") (pin "1") (pinfunction "1_1") (pintype "passive"))
      (node (ref "R47") (pin "2") (pinfunction "2_2") (pintype "passive"))
      (node (ref "T1") (pin "2") (pinfunction "S_2") (pintype "passive"))
      (node (ref "U1") (pin "P46") (pinfunction "IO_L28P_5D7_P46") (pintype "bidirectional"))
    )
    (net (code "59") (name "/PS2DAT") (class "Default")
      (node (ref "R51") (pin "2") (pinfunction "2_2") (pintype "passive"))
      (node (ref "R6") (pin "1") (pinfunction "1_1") (pintype "passive"))
      (node (ref "T3") (pin "2") (pinfunction "S_2") (pintype "passive"))
      (node (ref "U1") (pin "P44") (pinfunction "IOVREF_5_P44") (pintype "bidirectional"))
    )
    (net (code "60") (name "/R0") (class "Default")
      (node (ref "R10") (pin "1") (pinfunction "1_1") (pintype "passive"))
      (node (ref "U1") (pin "P55") (pinfunction "IO_L32P_4GCLK0_P55") (pintype "bidirectional"))
    )
    (net (code "61") (name "/R1") (class "Default")
      (node (ref "R9") (pin "1") (pinfunction "1_1") (pintype "passive"))
      (node (ref "U1") (pin "P53") (pinfunction "IO_L32N_5GCLK3_P53") (pintype "bidirectional"))
    )
    (net (code "62") (name "/SCART_BLANKING") (class "Default")
      (node (ref "R50") (pin "1") (pinfunction "1_1") (pintype "passive"))
      (node (ref "X1") (pin "16") (pinfunction "16_16") (pintype "passive"))
    )
    (net (code "63") (name "/SCART_BLUE") (class "Default")
      (node (ref "R31") (pin "1") (pinfunction "1_1") (pintype "passive"))
      (node (ref "R32") (pin "1") (pinfunction "1_1") (pintype "passive"))
      (node (ref "R33") (pin "1") (pinfunction "1_1") (pintype "passive"))
      (node (ref "X1") (pin "7") (pinfunction "7_7") (pintype "passive"))
    )
    (net (code "64") (name "/SCART_COMP") (class "Default")
      (node (ref "R13") (pin "1") (pinfunction "1_1") (pintype "passive"))
      (node (ref "R14") (pin "1") (pinfunction "1_1") (pintype "passive"))
      (node (ref "X1") (pin "19") (pinfunction "19_19") (pintype "passive"))
    )
    (net (code "65") (name "/SCART_GREEN") (class "Default")
      (node (ref "R26") (pin "1") (pinfunction "1_1") (pintype "passive"))
      (node (ref "R27") (pin "1") (pinfunction "1_1") (pintype "passive"))
      (node (ref "R28") (pin "1") (pinfunction "1_1") (pintype "passive"))
      (node (ref "X1") (pin "11") (pinfunction "11_11") (pintype "passive"))
    )
    (net (code "66") (name "/SCART_LEFT") (class "Default")
      (node (ref "C3") (pin "2") (pinfunction "2_2") (pintype "passive"))
      (node (ref "X1") (pin "3") (pinfunction "3_3") (pintype "passive"))
    )
    (net (code "67") (name "/SCART_MODE") (class "Default")
      (node (ref "X1") (pin "8") (pinfunction "8_8") (pintype "passive"))
    )
    (net (code "68") (name "/SCART_RED") (class "Default")
      (node (ref "R15") (pin "1") (pinfunction "1_1") (pintype "passive"))
      (node (ref "R16") (pin "1") (pinfunction "1_1") (pintype "passive"))
      (node (ref "R20") (pin "1") (pinfunction "1_1") (pintype "passive"))
      (node (ref "X1") (pin "15") (pinfunction "15_15") (pintype "passive"))
    )
    (net (code "69") (name "/SCART_RIGHT") (class "Default")
      (node (ref "C4") (pin "2") (pinfunction "2_2") (pintype "passive"))
      (node (ref "X1") (pin "1") (pinfunction "1_1") (pintype "passive"))
    )
    (net (code "70") (name "/SD_CLK") (class "Default")
      (node (ref "U$3") (pin "5") (pinfunction "SCLK_5") (pintype "input"))
      (node (ref "U1") (pin "P41") (pinfunction "IO_L01N_5RDWR_B_P41") (pintype "bidirectional"))
    )
    (net (code "71") (name "/SD_CS") (class "Default")
      (node (ref "U$3") (pin "1") (pinfunction "CS_1") (pintype "input"))
      (node (ref "U1") (pin "P141") (pinfunction "IO_L01N_0VRP_0_P141") (pintype "bidirectional"))
    )
    (net (code "72") (name "/SD_DI") (class "Default")
      (node (ref "U$3") (pin "2") (pinfunction "DATA_IN_2") (pintype "input"))
      (node (ref "U1") (pin "P140") (pinfunction "IO_L01P_0VRN_0_P140") (pintype "bidirectional"))
    )
    (net (code "73") (name "/SD_DO") (class "Default")
      (node (ref "U$3") (pin "7") (pinfunction "DATA_OUT_7") (pintype "output"))
      (node (ref "U1") (pin "P40") (pinfunction "IO_L01P_5CS_B_P40") (pintype "bidirectional"))
    )
    (net (code "74") (name "/SPI_MISO") (class "Default")
      (node (ref "IC3") (pin "17") (pinfunction "PB3(PDO/MISO/PCINT3)_17") (pintype "bidirectional"))
      (node (ref "SV1") (pin "16") (pinfunction "16_16") (pintype "passive"))
    )
    (net (code "75") (name "/SPI_MOSI") (class "Default")
      (node (ref "IC3") (pin "16") (pinfunction "PB2(PDI/MOSI/PCINT2)_16") (pintype "bidirectional"))
      (node (ref "SV1") (pin "20") (pinfunction "20_20") (pintype "passive"))
    )
    (net (code "76") (name "/SPI_SCLK") (class "Default")
      (node (ref "IC3") (pin "15") (pinfunction "PB1(SCK/PCINT1)_15") (pintype "bidirectional"))
      (node (ref "SV1") (pin "18") (pinfunction "18_18") (pintype "passive"))
    )
    (net (code "77") (name "/SPI_SEL") (class "Default")
      (node (ref "IC3") (pin "14") (pinfunction "PB0(SS/PCINT0)_14") (pintype "bidirectional"))
      (node (ref "SV1") (pin "14") (pinfunction "14_14") (pintype "passive"))
    )
    (net (code "78") (name "/TCK") (class "Default")
      (node (ref "IC1") (pin "6") (pinfunction "TCK_6") (pintype "bidirectional"))
      (node (ref "IC3") (pin "19") (pinfunction "PB5(PCINT5)_19") (pintype "bidirectional"))
      (node (ref "R2") (pin "2") (pinfunction "2_2") (pintype "passive"))
      (node (ref "SV1") (pin "9") (pinfunction "9_9") (pintype "passive"))
    )
    (net (code "79") (name "/TDI_FPGA") (class "Default")
      (node (ref "IC3") (pin "21") (pinfunction "PB7(OC0A/OC1C/PCINT7)_21") (pintype "bidirectional"))
      (node (ref "R1") (pin "2") (pinfunction "2_2") (pintype "passive"))
      (node (ref "SV1") (pin "7") (pinfunction "7_7") (pintype "passive"))
    )
    (net (code "80") (name "/TDO_EXP") (class "Default")
      (node (ref "IC3") (pin "23") (pinfunction "PC6(OC1A/PCINT8)_23") (pintype "bidirectional"))
      (node (ref "SV1") (pin "8") (pinfunction "8_8") (pintype "passive"))
    )
    (net (code "81") (name "/TDO_PROM") (class "Default")
      (node (ref "IC1") (pin "17") (pinfunction "TDO_17") (pintype "bidirectional"))
      (node (ref "IC3") (pin "20") (pinfunction "PB6(PCINT6)_20") (pintype "bidirectional"))
      (node (ref "SV1") (pin "10") (pinfunction "10_10") (pintype "passive"))
    )
    (net (code "82") (name "/TMS") (class "Default")
      (node (ref "IC1") (pin "5") (pinfunction "TMS_5") (pintype "bidirectional"))
      (node (ref "IC3") (pin "18") (pinfunction "PB4(T1/PCINT4)_18") (pintype "bidirectional"))
      (node (ref "R3") (pin "2") (pinfunction "2_2") (pintype "passive"))
      (node (ref "SV1") (pin "12") (pinfunction "12_12") (pintype "passive"))
    )
    (net (code "83") (name "/VCC") (class "Default")
      (node (ref "C10") (pin "1") (pinfunction "1_1") (pintype "passive"))
      (node (ref "C11") (pin "1") (pinfunction "1_1") (pintype "passive"))
      (node (ref "C12") (pin "1") (pinfunction "1_1") (pintype "passive"))
      (node (ref "C13") (pin "1") (pinfunction "1_1") (pintype "passive"))
      (node (ref "C14") (pin "1") (pinfunction "1_1") (pintype "passive"))
      (node (ref "C15") (pin "1") (pinfunction "1_1") (pintype "passive"))
      (node (ref "C16") (pin "1") (pinfunction "1_1") (pintype "passive"))
      (node (ref "C17") (pin "1") (pinfunction "1_1") (pintype "passive"))
      (node (ref "C26") (pin "1") (pinfunction "1_1") (pintype "passive"))
      (node (ref "C27") (pin "1") (pinfunction "1_1") (pintype "passive"))
      (node (ref "C29") (pin "1") (pinfunction "1_1") (pintype "passive"))
      (node (ref "C34") (pin "1") (pinfunction "1_1") (pintype "passive"))
      (node (ref "C39") (pin "+") (pinfunction "+_+") (pintype "passive"))
      (node (ref "C6") (pin "1") (pinfunction "1_1") (pintype "passive"))
      (node (ref "C7") (pin "1") (pinfunction "1_1") (pintype "passive"))
      (node (ref "C8") (pin "1") (pinfunction "1_1") (pintype "passive"))
      (node (ref "C9") (pin "1") (pinfunction "1_1") (pintype "passive"))
      (node (ref "IC1") (pin "18") (pinfunction "VCCINT_18") (pintype "bidirectional"))
      (node (ref "IC1") (pin "19") (pinfunction "VCCO_19") (pintype "bidirectional"))
      (node (ref "IC1") (pin "20") (pinfunction "VCCJ_20") (pintype "bidirectional"))
      (node (ref "IC2") (pin "8") (pinfunction "VCC_8") (pintype "power_in"))
      (node (ref "IC3") (pin "31") (pinfunction "UVCC_31") (pintype "bidirectional"))
      (node (ref "IC3") (pin "32") (pinfunction "AVCC_32") (pintype "bidirectional"))
      (node (ref "IC3") (pin "4") (pinfunction "VCC_4") (pintype "bidirectional"))
      (node (ref "Q5") (pin "3") (pinfunction "C_3") (pintype "passive"))
      (node (ref "Q6") (pin "3") (pinfunction "C_3") (pintype "passive"))
      (node (ref "Q7") (pin "3") (pinfunction "C_3") (pintype "passive"))
      (node (ref "Q8") (pin "3") (pinfunction "C_3") (pintype "passive"))
      (node (ref "R11") (pin "1") (pinfunction "1_1") (pintype "passive"))
      (node (ref "R22") (pin "1") (pinfunction "1_1") (pintype "passive"))
      (node (ref "R35") (pin "2") (pinfunction "2_2") (pintype "passive"))
      (node (ref "R36") (pin "2") (pinfunction "2_2") (pintype "passive"))
      (node (ref "R37") (pin "2") (pinfunction "2_2") (pintype "passive"))
      (node (ref "R38") (pin "2") (pinfunction "2_2") (pintype "passive"))
      (node (ref "R39") (pin "2") (pinfunction "2_2") (pintype "passive"))
      (node (ref "R4") (pin "2") (pinfunction "2_2") (pintype "passive"))
      (node (ref "R40") (pin "1") (pinfunction "1_1") (pintype "passive"))
      (node (ref "R41") (pin "1") (pinfunction "1_1") (pintype "passive"))
      (node (ref "R42") (pin "1") (pinfunction "1_1") (pintype "passive"))
      (node (ref "R43") (pin "1") (pinfunction "1_1") (pintype "passive"))
      (node (ref "R44") (pin "1") (pinfunction "1_1") (pintype "passive"))
      (node (ref "R45") (pin "1") (pinfunction "1_1") (pintype "passive"))
      (node (ref "R46") (pin "2") (pinfunction "2_2") (pintype "passive"))
      (node (ref "R55") (pin "1") (pinfunction "1_1") (pintype "passive"))
      (node (ref "R56") (pin "1") (pinfunction "1_1") (pintype "passive"))
      (node (ref "R6") (pin "2") (pinfunction "2_2") (pintype "passive"))
      (node (ref "SV1") (pin "3") (pinfunction "3_3") (pintype "passive"))
      (node (ref "SV1") (pin "4") (pinfunction "4_4") (pintype "passive"))
      (node (ref "SV2") (pin "4") (pinfunction "4_4") (pintype "passive"))
      (node (ref "SV2") (pin "6") (pinfunction "6_6") (pintype "passive"))
      (node (ref "SV3") (pin "1") (pinfunction "1_1") (pintype "passive"))
      (node (ref "SV5") (pin "7") (pinfunction "7_7") (pintype "passive"))
      (node (ref "SV5") (pin "8") (pinfunction "8_8") (pintype "passive"))
      (node (ref "T1") (pin "3") (pinfunction "G_3") (pintype "passive"))
      (node (ref "T2") (pin "3") (pinfunction "C_3") (pintype "passive"))
      (node (ref "T3") (pin "3") (pinfunction "G_3") (pintype "passive"))
      (node (ref "U$2") (pin "VDD") (pinfunction "VDD_VDD") (pintype "power_in"))
      (node (ref "U$3") (pin "4") (pinfunction "VDD_4") (pintype "power_in"))
      (node (ref "U$4") (pin "4") (pinfunction "VOUT1_4") (pintype "bidirectional"))
      (node (ref "U$6") (pin "P8") (pinfunction "VCC_P8") (pintype "bidirectional"))
      (node (ref "U1") (pin "P106") (pinfunction "VCCO_RIGHT2_P106") (pintype "passive"))
      (node (ref "U1") (pin "P115") (pinfunction "VCCO_TOP0_P115") (pintype "passive"))
      (node (ref "U1") (pin "P126") (pinfunction "VCCO_TOP1_P126") (pintype "passive"))
      (node (ref "U1") (pin "P138") (pinfunction "VCCO_TOP2_P138") (pintype "passive"))
      (node (ref "U1") (pin "P19") (pinfunction "VCCO_LEFT1_P19") (pintype "passive"))
      (node (ref "U1") (pin "P3") (pinfunction "VCCO_LEFT0_P3") (pintype "passive"))
      (node (ref "U1") (pin "P34") (pinfunction "VCCO_LEFT2_P34") (pintype "passive"))
      (node (ref "U1") (pin "P43") (pinfunction "VCCO_BOTTOM0_P43") (pintype "passive"))
      (node (ref "U1") (pin "P54") (pinfunction "VCCO_BOTTOM1_P54") (pintype "passive"))
      (node (ref "U1") (pin "P66") (pinfunction "VCCO_BOTTOM2_P66") (pintype "passive"))
      (node (ref "U1") (pin "P75") (pinfunction "VCCO_RIGHT0_P75") (pintype "passive"))
      (node (ref "U1") (pin "P91") (pinfunction "VCCO_RIGHT1_P91") (pintype "passive"))
    )
    (net (code "84") (name "/VCC5") (class "Default")
      (node (ref "C33") (pin "+") (pinfunction "+_+") (pintype "passive"))
      (node (ref "PWR_HDR") (pin "2") (pinfunction "2_2") (pintype "passive"))
      (node (ref "R5") (pin "2") (pinfunction "2_2") (pintype "passive"))
      (node (ref "R7") (pin "2") (pinfunction "2_2") (pintype "passive"))
      (node (ref "REG1.2") (pin "3") (pinfunction "VCC_3") (pintype "bidirectional"))
      (node (ref "REG2.5") (pin "3") (pinfunction "VCC_3") (pintype "bidirectional"))
      (node (ref "SV5") (pin "10") (pinfunction "10_10") (pintype "passive"))
      (node (ref "SV5") (pin "9") (pinfunction "9_9") (pintype "passive"))
      (node (ref "U$4") (pin "3") (pinfunction "VCC_3") (pintype "bidirectional"))
      (node (ref "X3") (pin "5") (pinfunction "5_5") (pintype "passive"))
      (node (ref "X7") (pin "2") (pinfunction "2_2") (pintype "power_in"))
    )
    (net (code "85") (name "/VCCAUX") (class "Default")
      (node (ref "C18") (pin "1") (pinfunction "1_1") (pintype "passive"))
      (node (ref "C19") (pin "1") (pinfunction "1_1") (pintype "passive"))
      (node (ref "C20") (pin "1") (pinfunction "1_1") (pintype "passive"))
      (node (ref "C21") (pin "1") (pinfunction "1_1") (pintype "passive"))
      (node (ref "C40") (pin "+") (pinfunction "+_+") (pintype "passive"))
      (node (ref "R50") (pin "2") (pinfunction "2_2") (pintype "passive"))
      (node (ref "REG2.5") (pin "4") (pinfunction "VOUT1_4") (pintype "bidirectional"))
      (node (ref "SV5") (pin "2") (pinfunction "2_2") (pintype "passive"))
      (node (ref "U1") (pin "P120") (pinfunction "VCCAUX2_P120") (pintype "passive"))
      (node (ref "U1") (pin "P134") (pinfunction "VCCAUX3_P134") (pintype "passive"))
      (node (ref "U1") (pin "P48") (pinfunction "VCCAUX0_P48") (pintype "passive"))
      (node (ref "U1") (pin "P62") (pinfunction "VCCAUX1_P62") (pintype "passive"))
    )
    (net (code "86") (name "/VCCINT") (class "Default")
      (node (ref "C22") (pin "1") (pinfunction "1_1") (pintype "passive"))
      (node (ref "C23") (pin "1") (pinfunction "1_1") (pintype "passive"))
      (node (ref "C24") (pin "1") (pinfunction "1_1") (pintype "passive"))
      (node (ref "C25") (pin "1") (pinfunction "1_1") (pintype "passive"))
      (node (ref "C42") (pin "+") (pinfunction "+_+") (pintype "passive"))
      (node (ref "REG1.2") (pin "4") (pinfunction "VOUT1_4") (pintype "bidirectional"))
      (node (ref "SV5") (pin "1") (pinfunction "1_1") (pintype "passive"))
      (node (ref "U1") (pin "P121") (pinfunction "VCCINT2_P121") (pintype "passive"))
      (node (ref "U1") (pin "P133") (pinfunction "VCCINT3_P133") (pintype "passive"))
      (node (ref "U1") (pin "P49") (pinfunction "VCCINT0_P49") (pintype "passive"))
      (node (ref "U1") (pin "P61") (pinfunction "VCCINT1_P61") (pintype "passive"))
    )
    (net (code "87") (name "/X3") (class "Default")
      (node (ref "SV2") (pin "5") (pinfunction "5_5") (pintype "passive"))
      (node (ref "U1") (pin "P76") (pinfunction "IO_P76") (pintype "bidirectional"))
    )
    (net (code "88") (name "/X4") (class "Default")
      (node (ref "SV2") (pin "3") (pinfunction "3_3") (pintype "passive"))
      (node (ref "U1") (pin "P77") (pinfunction "IO_L20P_3_P77") (pintype "bidirectional"))
    )
    (net (code "89") (name "/X8") (class "Default")
      (node (ref "SV2") (pin "1") (pinfunction "1_1") (pintype "passive"))
      (node (ref "U1") (pin "P74") (pinfunction "IO_L01N_3VRP_3_P74") (pintype "bidirectional"))
    )
    (net (code "91") (name "GND") (class "Default")
      (node (ref "C1") (pin "1") (pinfunction "1_1") (pintype "passive"))
      (node (ref "C10") (pin "2") (pinfunction "2_2") (pintype "passive"))
      (node (ref "C11") (pin "2") (pinfunction "2_2") (pintype "passive"))
      (node (ref "C12") (pin "2") (pinfunction "2_2") (pintype "passive"))
      (node (ref "C13") (pin "2") (pinfunction "2_2") (pintype "passive"))
      (node (ref "C14") (pin "2") (pinfunction "2_2") (pintype "passive"))
      (node (ref "C15") (pin "2") (pinfunction "2_2") (pintype "passive"))
      (node (ref "C16") (pin "2") (pinfunction "2_2") (pintype "passive"))
      (node (ref "C17") (pin "2") (pinfunction "2_2") (pintype "passive"))
      (node (ref "C18") (pin "2") (pinfunction "2_2") (pintype "passive"))
      (node (ref "C19") (pin "2") (pinfunction "2_2") (pintype "passive"))
      (node (ref "C20") (pin "2") (pinfunction "2_2") (pintype "passive"))
      (node (ref "C21") (pin "2") (pinfunction "2_2") (pintype "passive"))
      (node (ref "C22") (pin "2") (pinfunction "2_2") (pintype "passive"))
      (node (ref "C23") (pin "2") (pinfunction "2_2") (pintype "passive"))
      (node (ref "C24") (pin "2") (pinfunction "2_2") (pintype "passive"))
      (node (ref "C25") (pin "2") (pinfunction "2_2") (pintype "passive"))
      (node (ref "C26") (pin "2") (pinfunction "2_2") (pintype "passive"))
      (node (ref "C27") (pin "2") (pinfunction "2_2") (pintype "passive"))
      (node (ref "C29") (pin "2") (pinfunction "2_2") (pintype "passive"))
      (node (ref "C33") (pin "-") (pinfunction "-_-") (pintype "passive"))
      (node (ref "C34") (pin "2") (pinfunction "2_2") (pintype "passive"))
      (node (ref "C37") (pin "1") (pinfunction "1_1") (pintype "passive"))
      (node (ref "C38") (pin "1") (pinfunction "1_1") (pintype "passive"))
      (node (ref "C39") (pin "-") (pinfunction "-_-") (pintype "passive"))
      (node (ref "C40") (pin "-") (pinfunction "-_-") (pintype "passive"))
      (node (ref "C41") (pin "2") (pinfunction "2_2") (pintype "passive"))
      (node (ref "C42") (pin "-") (pinfunction "-_-") (pintype "passive"))
      (node (ref "C5") (pin "1") (pinfunction "1_1") (pintype "passive"))
      (node (ref "C6") (pin "2") (pinfunction "2_2") (pintype "passive"))
      (node (ref "C7") (pin "2") (pinfunction "2_2") (pintype "passive"))
      (node (ref "C8") (pin "2") (pinfunction "2_2") (pintype "passive"))
      (node (ref "C9") (pin "2") (pinfunction "2_2") (pintype "passive"))
      (node (ref "IC1") (pin "11") (pinfunction "GND_11") (pintype "bidirectional"))
      (node (ref "IC2") (pin "4") (pinfunction "GND_4") (pintype "power_in"))
      (node (ref "IC3") (pin "3") (pinfunction "GND_3") (pintype "bidirectional"))
      (node (ref "LED1") (pin "C") (pinfunction "C_C") (pintype "passive"))
      (node (ref "PWR_HDR") (pin "1") (pinfunction "1_1") (pintype "passive"))
      (node (ref "R17") (pin "1") (pinfunction "1_1") (pintype "passive"))
      (node (ref "R19") (pin "1") (pinfunction "1_1") (pintype "passive"))
      (node (ref "R21") (pin "1") (pinfunction "1_1") (pintype "passive"))
      (node (ref "REG1.2") (pin "1") (pinfunction "GND_1") (pintype "bidirectional"))
      (node (ref "REG2.5") (pin "1") (pinfunction "GND_1") (pintype "bidirectional"))
      (node (ref "SV1") (pin "5") (pinfunction "5_5") (pintype "passive"))
      (node (ref "SV1") (pin "6") (pinfunction "6_6") (pintype "passive"))
      (node (ref "SV2") (pin "2") (pinfunction "2_2") (pintype "passive"))
      (node (ref "SV3") (pin "2") (pinfunction "2_2") (pintype "passive"))
      (node (ref "SV5") (pin "3") (pinfunction "3_3") (pintype "passive"))
      (node (ref "U$1") (pin "GND") (pinfunction "GND_GND") (pintype "bidirectional"))
      (node (ref "U$2") (pin "GND") (pinfunction "GND_GND") (pintype "power_in"))
      (node (ref "U$3") (pin "3") (pinfunction "VSS1_3") (pintype "power_in"))
      (node (ref "U$3") (pin "6") (pinfunction "VSS2_6") (pintype "power_in"))
      (node (ref "U$3") (pin "MT1") (pinfunction "COMMON_SW_MT1") (pintype "passive"))
      (node (ref "U$3") (pin "MT3") (pinfunction "GND_MT3") (pintype "power_in"))
      (node (ref "U$4") (pin "1") (pinfunction "GND_1") (pintype "bidirectional"))
      (node (ref "U$6") (pin "P24") (pinfunction "VSS_P24") (pintype "bidirectional"))
      (node (ref "U$6") (pin "P30") (pinfunction "CE_P30") (pintype "bidirectional"))
      (node (ref "U$7") (pin "GND") (pinfunction "GND_GND") (pintype "bidirectional"))
      (node (ref "U$8") (pin "GND") (pinfunction "GND_GND") (pintype "bidirectional"))
      (node (ref "U$9") (pin "GND") (pinfunction "GND_GND") (pintype "bidirectional"))
      (node (ref "U1") (pin "P101") (pinfunction "GND11_P101") (pintype "passive"))
      (node (ref "U1") (pin "P114") (pinfunction "GND12_P114") (pintype "passive"))
      (node (ref "U1") (pin "P117") (pinfunction "GND13_P117") (pintype "passive"))
      (node (ref "U1") (pin "P136") (pinfunction "GND14_P136") (pintype "passive"))
      (node (ref "U1") (pin "P139") (pinfunction "GND15_P139") (pintype "passive"))
      (node (ref "U1") (pin "P16") (pinfunction "GND1_P16") (pintype "passive"))
      (node (ref "U1") (pin "P22") (pinfunction "GND2_P22") (pintype "passive"))
      (node (ref "U1") (pin "P29") (pinfunction "GND3_P29") (pintype "passive"))
      (node (ref "U1") (pin "P37") (pinfunction "M1_P37") (pintype "bidirectional"))
      (node (ref "U1") (pin "P38") (pinfunction "M0_P38") (pintype "bidirectional"))
      (node (ref "U1") (pin "P39") (pinfunction "M2_P39") (pintype "bidirectional"))
      (node (ref "U1") (pin "P42") (pinfunction "GND4_P42") (pintype "passive"))
      (node (ref "U1") (pin "P45") (pinfunction "GND5_P45") (pintype "passive"))
      (node (ref "U1") (pin "P64") (pinfunction "GND6_P64") (pintype "passive"))
      (node (ref "U1") (pin "P67") (pinfunction "GND7_P67") (pintype "passive"))
      (node (ref "U1") (pin "P81") (pinfunction "GND8_P81") (pintype "passive"))
      (node (ref "U1") (pin "P88") (pinfunction "GND9_P88") (pintype "passive"))
      (node (ref "U1") (pin "P9") (pinfunction "GND0_P9") (pintype "passive"))
      (node (ref "U1") (pin "P94") (pinfunction "GND10_P94") (pintype "passive"))
      (node (ref "X1") (pin "13") (pinfunction "13_13") (pintype "passive"))
      (node (ref "X1") (pin "14") (pinfunction "14_14") (pintype "passive"))
      (node (ref "X1") (pin "17") (pinfunction "17_17") (pintype "passive"))
      (node (ref "X1") (pin "18") (pinfunction "18_18") (pintype "passive"))
      (node (ref "X1") (pin "21") (pinfunction "21_21") (pintype "passive"))
      (node (ref "X1") (pin "4") (pinfunction "4_4") (pintype "passive"))
      (node (ref "X1") (pin "5") (pinfunction "5_5") (pintype "passive"))
      (node (ref "X1") (pin "9") (pinfunction "9_9") (pintype "passive"))
      (node (ref "X3") (pin "3") (pinfunction "3_3") (pintype "passive"))
      (node (ref "X3") (pin "SH1") (pinfunction "PE1_SH1") (pintype "power_in"))
      (node (ref "X3") (pin "SH2") (pinfunction "PE2_SH2") (pintype "power_in"))
      (node (ref "X3") (pin "SH3") (pinfunction "PE3_SH3") (pintype "power_in"))
      (node (ref "X4") (pin "8") (pinfunction "F_8") (pintype "passive"))
      (node (ref "X4") (pin "G1") (pinfunction "G1_G1") (pintype "passive"))
      (node (ref "X5") (pin "8") (pinfunction "F_8") (pintype "passive"))
      (node (ref "X5") (pin "G1") (pinfunction "G1_G1") (pintype "passive"))
      (node (ref "X7") (pin "3") (pinfunction "3_3") (pintype "power_in"))
      (node (ref "X8") (pin "1") (pinfunction "1_1") (pintype "passive"))
    )
    (net (code "92") (name "Net-(C1-Pad2)") (class "Default")
      (node (ref "C1") (pin "2") (pinfunction "2_2") (pintype "passive"))
      (node (ref "R23") (pin "2") (pinfunction "2_2") (pintype "passive"))
      (node (ref "R48") (pin "1") (pinfunction "1_1") (pintype "passive"))
    )
    (net (code "93") (name "Net-(C2-Pad1)") (class "Default")
      (node (ref "C2") (pin "1") (pinfunction "1_1") (pintype "passive"))
      (node (ref "R17") (pin "2") (pinfunction "2_2") (pintype "passive"))
      (node (ref "X8") (pin "2") (pinfunction "2_2") (pintype "passive"))
      (node (ref "X8") (pin "3") (pinfunction "3_3") (pintype "passive"))
      (node (ref "X8") (pin "4") (pinfunction "4_4") (pintype "passive"))
      (node (ref "X8") (pin "5") (pinfunction "5_5") (pintype "passive"))
    )
    (net (code "94") (name "Net-(C3-Pad1)") (class "Default")
      (node (ref "C3") (pin "1") (pinfunction "1_1") (pintype "passive"))
      (node (ref "R48") (pin "2") (pinfunction "2_2") (pintype "passive"))
    )
    (net (code "95") (name "Net-(C4-Pad1)") (class "Default")
      (node (ref "C4") (pin "1") (pinfunction "1_1") (pintype "passive"))
      (node (ref "R49") (pin "2") (pinfunction "2_2") (pintype "passive"))
    )
    (net (code "96") (name "Net-(C5-Pad2)") (class "Default")
      (node (ref "C5") (pin "2") (pinfunction "2_2") (pintype "passive"))
      (node (ref "R34") (pin "2") (pinfunction "2_2") (pintype "passive"))
      (node (ref "R49") (pin "1") (pinfunction "1_1") (pintype "passive"))
    )
    (net (code "97") (name "Net-(C38-Pad2)") (class "Default")
      (node (ref "C38") (pin "2") (pinfunction "2_2") (pintype "passive"))
      (node (ref "JP2") (pin "1") (pinfunction "1_1") (pintype "passive"))
      (node (ref "Q1") (pin "2") (pinfunction "2_2") (pintype "passive"))
    )
    (net (code "98") (name "Net-(IC1-CLK)") (class "Default")
      (node (ref "IC1") (pin "3") (pinfunction "CLK_3") (pintype "bidirectional"))
      (node (ref "U1") (pin "P72") (pinfunction "CCLK_P72") (pintype "bidirectional"))
    )
    (net (code "99") (name "Net-(IC1-TDI)") (class "Default")
      (node (ref "IC1") (pin "4") (pinfunction "TDI_4") (pintype "bidirectional"))
      (node (ref "U1") (pin "P109") (pinfunction "TDO_P109") (pintype "bidirectional"))
    )
    (net (code "100") (name "Net-(IC1-{slash}CE)") (class "Default")
      (node (ref "IC1") (pin "10") (pinfunction "/CE_10") (pintype "bidirectional"))
      (node (ref "U1") (pin "P71") (pinfunction "DONE_P71") (pintype "bidirectional"))
    )
    (net (code "101") (name "Net-(IC1-{slash}CF)") (class "Default")
      (node (ref "IC1") (pin "7") (pinfunction "/CF_7") (pintype "bidirectional"))
      (node (ref "U1") (pin "P143") (pinfunction "PROG_B_P143") (pintype "bidirectional"))
    )
    (net (code "102") (name "Net-(IC3-D+)") (class "Default")
      (node (ref "IC3") (pin "29") (pinfunction "D+_29") (pintype "bidirectional"))
      (node (ref "R54") (pin "2") (pinfunction "2_2") (pintype "passive"))
    )
    (net (code "103") (name "Net-(IC3-D-)") (class "Default")
      (node (ref "IC3") (pin "30") (pinfunction "D-_30") (pintype "bidirectional"))
      (node (ref "R53") (pin "2") (pinfunction "2_2") (pintype "passive"))
    )
    (net (code "104") (name "Net-(IC3-UCAP)") (class "Default")
      (node (ref "C41") (pin "1") (pinfunction "1_1") (pintype "passive"))
      (node (ref "IC3") (pin "27") (pinfunction "UCAP_27") (pintype "bidirectional"))
    )
    (net (code "105") (name "Net-(IC3-UGND)") (class "Default")
      (node (ref "IC3") (pin "28") (pinfunction "UGND_28") (pintype "bidirectional"))
      (node (ref "X6") (pin "4") (pinfunction "4_4") (pintype "passive"))
    )
    (net (code "106") (name "Net-(IC3-XTAL1)") (class "Default")
      (node (ref "IC3") (pin "1") (pinfunction "XTAL1_1") (pintype "bidirectional"))
      (node (ref "JP2") (pin "2") (pinfunction "2_2") (pintype "passive"))
    )
    (net (code "107") (name "Net-(IC3-XTAL2{slash}PC0)") (class "Default")
      (node (ref "C37") (pin "2") (pinfunction "2_2") (pintype "passive"))
      (node (ref "IC3") (pin "2") (pinfunction "XTAL2/PC0_2") (pintype "bidirectional"))
      (node (ref "Q1") (pin "1") (pinfunction "1_1") (pintype "passive"))
    )
    (net (code "108") (name "Net-(LED1-PadA)") (class "Default")
      (node (ref "LED1") (pin "A") (pinfunction "A_A") (pintype "passive"))
      (node (ref "R11") (pin "2") (pinfunction "2_2") (pintype "passive"))
    )
    (net (code "109") (name "Net-(Q5-B)") (class "Default")
      (node (ref "Q5") (pin "1") (pinfunction "B_1") (pintype "passive"))
      (node (ref "R8") (pin "2") (pinfunction "2_2") (pintype "passive"))
    )
    (net (code "110") (name "Net-(Q5-E)") (class "Default")
      (node (ref "Q5") (pin "2") (pinfunction "E_2") (pintype "passive"))
      (node (ref "R13") (pin "2") (pinfunction "2_2") (pintype "passive"))
      (node (ref "R14") (pin "2") (pinfunction "2_2") (pintype "passive"))
    )
    (net (code "111") (name "Net-(Q6-B)") (class "Default")
      (node (ref "Q6") (pin "1") (pinfunction "B_1") (pintype "passive"))
      (node (ref "R10") (pin "2") (pinfunction "2_2") (pintype "passive"))
      (node (ref "R9") (pin "2") (pinfunction "2_2") (pintype "passive"))
    )
    (net (code "112") (name "Net-(Q6-E)") (class "Default")
      (node (ref "Q6") (pin "2") (pinfunction "E_2") (pintype "passive"))
      (node (ref "R15") (pin "2") (pinfunction "2_2") (pintype "passive"))
      (node (ref "R16") (pin "2") (pinfunction "2_2") (pintype "passive"))
      (node (ref "R20") (pin "2") (pinfunction "2_2") (pintype "passive"))
    )
    (net (code "113") (name "Net-(Q7-B)") (class "Default")
      (node (ref "Q7") (pin "1") (pinfunction "B_1") (pintype "passive"))
      (node (ref "R29") (pin "2") (pinfunction "2_2") (pintype "passive"))
      (node (ref "R30") (pin "2") (pinfunction "2_2") (pintype "passive"))
    )
    (net (code "114") (name "Net-(Q7-E)") (class "Default")
      (node (ref "Q7") (pin "2") (pinfunction "E_2") (pintype "passive"))
      (node (ref "R31") (pin "2") (pinfunction "2_2") (pintype "passive"))
      (node (ref "R32") (pin "2") (pinfunction "2_2") (pintype "passive"))
      (node (ref "R33") (pin "2") (pinfunction "2_2") (pintype "passive"))
    )
    (net (code "115") (name "Net-(Q8-B)") (class "Default")
      (node (ref "Q8") (pin "1") (pinfunction "B_1") (pintype "passive"))
      (node (ref "R24") (pin "2") (pinfunction "2_2") (pintype "passive"))
      (node (ref "R25") (pin "2") (pinfunction "2_2") (pintype "passive"))
    )
    (net (code "116") (name "Net-(Q8-E)") (class "Default")
      (node (ref "Q8") (pin "2") (pinfunction "E_2") (pintype "passive"))
      (node (ref "R26") (pin "2") (pinfunction "2_2") (pintype "passive"))
      (node (ref "R27") (pin "2") (pinfunction "2_2") (pintype "passive"))
      (node (ref "R28") (pin "2") (pinfunction "2_2") (pintype "passive"))
    )
    (net (code "117") (name "Net-(R18-Pad2)") (class "Default")
      (node (ref "R18") (pin "2") (pinfunction "2_2") (pintype "passive"))
      (node (ref "R22") (pin "2") (pinfunction "2_2") (pintype "passive"))
    )
    (net (code "118") (name "Net-(R53-Pad1)") (class "Default")
      (node (ref "R53") (pin "1") (pinfunction "1_1") (pintype "passive"))
      (node (ref "X6") (pin "2") (pinfunction "2_2") (pintype "passive"))
    )
    (net (code "119") (name "Net-(R54-Pad1)") (class "Default")
      (node (ref "R54") (pin "1") (pinfunction "1_1") (pintype "passive"))
      (node (ref "X6") (pin "3") (pinfunction "3_3") (pintype "passive"))
    )
    (net (code "120") (name "Net-(T2-B)") (class "Default")
      (node (ref "C2") (pin "2") (pinfunction "2_2") (pintype "passive"))
      (node (ref "R18") (pin "1") (pinfunction "1_1") (pintype "passive"))
      (node (ref "R19") (pin "2") (pinfunction "2_2") (pintype "passive"))
      (node (ref "T2") (pin "1") (pinfunction "B_1") (pintype "passive"))
    )
    (net (code "121") (name "Net-(U$6-A0)") (class "Default")
      (node (ref "U$6") (pin "P20") (pinfunction "A0_P20") (pintype "bidirectional"))
      (node (ref "U1") (pin "P24") (pinfunction "IO_L24N_6VREF_6_P24") (pintype "bidirectional"))
    )
    (net (code "122") (name "Net-(U$6-A1)") (class "Default")
      (node (ref "U$6") (pin "P19") (pinfunction "A1_P19") (pintype "bidirectional"))
      (node (ref "U1") (pin "P23") (pinfunction "IO_L24P_6_P23") (pintype "bidirectional"))
    )
    (net (code "123") (name "Net-(U$6-A2)") (class "Default")
      (node (ref "U$6") (pin "P18") (pinfunction "A2_P18") (pintype "bidirectional"))
      (node (ref "U1") (pin "P21") (pinfunction "IO_L40N_6_P21") (pintype "bidirectional"))
    )
    (net (code "124") (name "Net-(U$6-A3)") (class "Default")
      (node (ref "U$6") (pin "P17") (pinfunction "A3_P17") (pintype "bidirectional"))
      (node (ref "U1") (pin "P20") (pinfunction "IO_L40P_6VREF_6_P20") (pintype "bidirectional"))
    )
    (net (code "125") (name "Net-(U$6-A4)") (class "Default")
      (node (ref "U$6") (pin "P16") (pinfunction "A4_P16") (pintype "bidirectional"))
      (node (ref "U1") (pin "P18") (pinfunction "IO_L40N_7VREF_7_P18") (pintype "bidirectional"))
    )
    (net (code "126") (name "Net-(U$6-A5)") (class "Default")
      (node (ref "U$6") (pin "P15") (pinfunction "A5_P15") (pintype "bidirectional"))
      (node (ref "U1") (pin "P17") (pinfunction "IO_L40P_7_P17") (pintype "bidirectional"))
    )
    (net (code "127") (name "Net-(U$6-A6)") (class "Default")
      (node (ref "U$6") (pin "P14") (pinfunction "A6_P14") (pintype "bidirectional"))
      (node (ref "U1") (pin "P15") (pinfunction "IO_L24N_7_P15") (pintype "bidirectional"))
    )
    (net (code "128") (name "Net-(U$6-A7)") (class "Default")
      (node (ref "U$6") (pin "P13") (pinfunction "A7_P13") (pintype "bidirectional"))
      (node (ref "U1") (pin "P14") (pinfunction "IO_L24P_7_P14") (pintype "bidirectional"))
    )
    (net (code "129") (name "Net-(U$6-A8)") (class "Default")
      (node (ref "U$6") (pin "P3") (pinfunction "A8_P3") (pintype "bidirectional"))
      (node (ref "U1") (pin "P4") (pinfunction "IOVREF_7_P4") (pintype "bidirectional"))
    )
    (net (code "130") (name "Net-(U$6-A9)") (class "Default")
      (node (ref "U$6") (pin "P2") (pinfunction "A9_P2") (pintype "bidirectional"))
      (node (ref "U1") (pin "P2") (pinfunction "IO_L01N_7VRP_7_P2") (pintype "bidirectional"))
    )
    (net (code "131") (name "Net-(U$6-A10)") (class "Default")
      (node (ref "U$6") (pin "P31") (pinfunction "A10_P31") (pintype "bidirectional"))
      (node (ref "U1") (pin "P35") (pinfunction "IO_L01P_6VRN_6_P35") (pintype "bidirectional"))
    )
    (net (code "132") (name "Net-(U$6-A11)") (class "Default")
      (node (ref "U$6") (pin "P1") (pinfunction "A11_P1") (pintype "bidirectional"))
      (node (ref "U1") (pin "P1") (pinfunction "IO_L01P_7VRN_7_P1") (pintype "bidirectional"))
    )
    (net (code "133") (name "Net-(U$6-A12)") (class "Default")
      (node (ref "U$6") (pin "P12") (pinfunction "A12_P12") (pintype "bidirectional"))
      (node (ref "U1") (pin "P13") (pinfunction "IO_L23N_7_P13") (pintype "bidirectional"))
    )
    (net (code "134") (name "Net-(U$6-A13)") (class "Default")
      (node (ref "U$6") (pin "P4") (pinfunction "A13_P4") (pintype "bidirectional"))
      (node (ref "U1") (pin "P5") (pinfunction "IO_L20P_7_P5") (pintype "bidirectional"))
    )
    (net (code "135") (name "Net-(U$6-A14)") (class "Default")
      (node (ref "U$6") (pin "P11") (pinfunction "A14_P11") (pintype "bidirectional"))
      (node (ref "U1") (pin "P12") (pinfunction "IO_L23P_7_P12") (pintype "bidirectional"))
    )
    (net (code "136") (name "Net-(U$6-A15)") (class "Default")
      (node (ref "U$6") (pin "P7") (pinfunction "A15_P7") (pintype "bidirectional"))
      (node (ref "U1") (pin "P8") (pinfunction "IO_L21N_7_P8") (pintype "bidirectional"))
    )
    (net (code "137") (name "Net-(U$6-A16)") (class "Default")
      (node (ref "U$6") (pin "P10") (pinfunction "A16_P10") (pintype "bidirectional"))
      (node (ref "U1") (pin "P11") (pinfunction "IO_L22N_7_P11") (pintype "bidirectional"))
    )
    (net (code "138") (name "Net-(U$6-A17)") (class "Default")
      (node (ref "U$6") (pin "P6") (pinfunction "A17_P6") (pintype "bidirectional"))
      (node (ref "U1") (pin "P7") (pinfunction "IO_L21P_7_P7") (pintype "bidirectional"))
    )
    (net (code "139") (name "Net-(U$6-A18)") (class "Default")
      (node (ref "U$6") (pin "P9") (pinfunction "A18_P9") (pintype "bidirectional"))
      (node (ref "U1") (pin "P10") (pinfunction "IO_L22P_7_P10") (pintype "bidirectional"))
    )
    (net (code "140") (name "Net-(U$6-DQ0)") (class "Default")
      (node (ref "U$6") (pin "P21") (pinfunction "DQ0_P21") (pintype "bidirectional"))
      (node (ref "U1") (pin "P25") (pinfunction "IO_L23P_6_P25") (pintype "bidirectional"))
    )
    (net (code "141") (name "Net-(U$6-DQ1)") (class "Default")
      (node (ref "U$6") (pin "P22") (pinfunction "DQ1_P22") (pintype "bidirectional"))
      (node (ref "U1") (pin "P26") (pinfunction "IO_L23N_6_P26") (pintype "bidirectional"))
    )
    (net (code "142") (name "Net-(U$6-DQ2)") (class "Default")
      (node (ref "U$6") (pin "P23") (pinfunction "DQ2_P23") (pintype "bidirectional"))
      (node (ref "U1") (pin "P27") (pinfunction "IO_L22P_6_P27") (pintype "bidirectional"))
    )
    (net (code "143") (name "Net-(U$6-DQ3)") (class "Default")
      (node (ref "U$6") (pin "P25") (pinfunction "DQ3_P25") (pintype "bidirectional"))
      (node (ref "U1") (pin "P28") (pinfunction "IO_L22N_6_P28") (pintype "bidirectional"))
    )
    (net (code "144") (name "Net-(U$6-DQ4)") (class "Default")
      (node (ref "U$6") (pin "P26") (pinfunction "DQ4_P26") (pintype "bidirectional"))
      (node (ref "U1") (pin "P30") (pinfunction "IO_L21P_6_P30") (pintype "bidirectional"))
    )
    (net (code "145") (name "Net-(U$6-DQ5)") (class "Default")
      (node (ref "U$6") (pin "P27") (pinfunction "DQ5_P27") (pintype "bidirectional"))
      (node (ref "U1") (pin "P31") (pinfunction "IO_L21N_6_P31") (pintype "bidirectional"))
    )
    (net (code "146") (name "Net-(U$6-DQ6)") (class "Default")
      (node (ref "U$6") (pin "P28") (pinfunction "DQ6_P28") (pintype "bidirectional"))
      (node (ref "U1") (pin "P32") (pinfunction "IO_L20P_6_P32") (pintype "bidirectional"))
    )
    (net (code "147") (name "Net-(U$6-DQ7)") (class "Default")
      (node (ref "U$6") (pin "P29") (pinfunction "DQ7_P29") (pintype "bidirectional"))
      (node (ref "U1") (pin "P33") (pinfunction "IO_L20N_6_P33") (pintype "bidirectional"))
    )
    (net (code "148") (name "Net-(U$6-OE)") (class "Default")
      (node (ref "U$6") (pin "P32") (pinfunction "OE_P32") (pintype "bidirectional"))
      (node (ref "U1") (pin "P36") (pinfunction "IO_L01N_6VRP_6_P36") (pintype "bidirectional"))
    )
    (net (code "149") (name "Net-(U$6-WE)") (class "Default")
      (node (ref "U$6") (pin "P5") (pinfunction "WE_P5") (pintype "bidirectional"))
      (node (ref "U1") (pin "P6") (pinfunction "IO_L20N_7_P6") (pintype "bidirectional"))
    )
    (net (code "150") (name "Net-(U1A-IO_L27N_0)") (class "Default")
      (node (ref "SV3") (pin "3") (pinfunction "3_3") (pintype "passive"))
      (node (ref "U1") (pin "P137") (pinfunction "IO_L27N_0_P137") (pintype "bidirectional"))
    )
    (net (code "151") (name "Net-(U1A-IO_L27P_0)") (class "Default")
      (node (ref "SV3") (pin "4") (pinfunction "4_4") (pintype "passive"))
      (node (ref "U1") (pin "P135") (pinfunction "IO_L27P_0_P135") (pintype "bidirectional"))
    )
    (net (code "152") (name "Net-(U1A-IO_L30N_0)") (class "Default")
      (node (ref "SV3") (pin "5") (pinfunction "5_5") (pintype "passive"))
      (node (ref "U1") (pin "P132") (pinfunction "IO_L30N_0_P132") (pintype "bidirectional"))
    )
    (net (code "153") (name "Net-(U1A-IO_L31N_0)") (class "Default")
      (node (ref "SV3") (pin "6") (pinfunction "6_6") (pintype "passive"))
      (node (ref "U1") (pin "P130") (pinfunction "IO_L31N_0_P130") (pintype "bidirectional"))
    )
    (net (code "154") (name "Net-(U1A-IO_L31P_0VREF_0)") (class "Default")
      (node (ref "SV3") (pin "7") (pinfunction "7_7") (pintype "passive"))
      (node (ref "U1") (pin "P129") (pinfunction "IO_L31P_0VREF_0_P129") (pintype "bidirectional"))
    )
    (net (code "155") (name "Net-(U1A-IO_L32N_0GCLK7)") (class "Default")
      (node (ref "SV3") (pin "9") (pinfunction "9_9") (pintype "passive"))
      (node (ref "U1") (pin "P128") (pinfunction "IO_L32N_0GCLK7_P128") (pintype "bidirectional"))
    )
    (net (code "156") (name "Net-(U1A-IO_L32P_0GCLK6)") (class "Default")
      (node (ref "SV3") (pin "8") (pinfunction "8_8") (pintype "passive"))
      (node (ref "U1") (pin "P127") (pinfunction "IO_L32P_0GCLK6_P127") (pintype "bidirectional"))
    )
    (net (code "157") (name "Net-(U1C-IO_L31N_1VREF_1)") (class "Default")
      (node (ref "SV3") (pin "10") (pinfunction "10_10") (pintype "passive"))
      (node (ref "U1") (pin "P123") (pinfunction "IO_L31N_1VREF_1_P123") (pintype "bidirectional"))
    )
    (net (code "158") (name "Net-(U1N-TCK)") (class "Default")
      (node (ref "R2") (pin "1") (pinfunction "1_1") (pintype "passive"))
      (node (ref "U1") (pin "P110") (pinfunction "TCK_P110") (pintype "bidirectional"))
    )
    (net (code "159") (name "Net-(U1N-TDI)") (class "Default")
      (node (ref "R1") (pin "1") (pinfunction "1_1") (pintype "passive"))
      (node (ref "U1") (pin "P144") (pinfunction "TDI_P144") (pintype "bidirectional"))
    )
    (net (code "160") (name "Net-(U1N-TMS)") (class "Default")
      (node (ref "R3") (pin "1") (pinfunction "1_1") (pintype "passive"))
      (node (ref "U1") (pin "P111") (pinfunction "TMS_P111") (pintype "bidirectional"))
    )
    (net (code "161") (name "unconnected-(IC1-NC.1-Pad2)") (class "Default")
      (node (ref "IC1") (pin "2") (pinfunction "NC.1_2") (pintype "bidirectional"))
    )
    (net (code "162") (name "unconnected-(IC1-NC.2-Pad9)") (class "Default")
      (node (ref "IC1") (pin "9") (pinfunction "NC.2_9") (pintype "bidirectional"))
    )
    (net (code "163") (name "unconnected-(IC1-NC.3-Pad12)") (class "Default")
      (node (ref "IC1") (pin "12") (pinfunction "NC.3_12") (pintype "bidirectional"))
    )
    (net (code "164") (name "unconnected-(IC1-NC.4-Pad14)") (class "Default")
      (node (ref "IC1") (pin "14") (pinfunction "NC.4_14") (pintype "bidirectional"))
    )
    (net (code "165") (name "unconnected-(IC1-NC.5-Pad15)") (class "Default")
      (node (ref "IC1") (pin "15") (pinfunction "NC.5_15") (pintype "bidirectional"))
    )
    (net (code "166") (name "unconnected-(IC1-NC.6-Pad16)") (class "Default")
      (node (ref "IC1") (pin "16") (pinfunction "NC.6_16") (pintype "bidirectional"))
    )
    (net (code "167") (name "unconnected-(IC1-{slash}CEO-Pad13)") (class "Default")
      (node (ref "IC1") (pin "13") (pinfunction "/CEO_13") (pintype "bidirectional"))
    )
    (net (code "168") (name "unconnected-(REG1.2-VOUT2-Pad2)") (class "Default")
      (node (ref "REG1.2") (pin "2") (pinfunction "VOUT2_2") (pintype "bidirectional"))
    )
    (net (code "169") (name "unconnected-(REG2.5-VOUT2-Pad2)") (class "Default")
      (node (ref "REG2.5") (pin "2") (pinfunction "VOUT2_2") (pintype "bidirectional"))
    )
    (net (code "170") (name "unconnected-(U$2-TRI-PadENA)") (class "Default")
      (node (ref "U$2") (pin "ENA") (pinfunction "TRI_ENA") (pintype "input"))
    )
    (net (code "171") (name "unconnected-(U$3-CARD_DETECT-PadCD)") (class "Default")
      (node (ref "U$3") (pin "CD") (pinfunction "CARD_DETECT_CD") (pintype "passive"))
    )
    (net (code "172") (name "unconnected-(U$3-DAT1-Pad8)") (class "Default")
      (node (ref "U$3") (pin "8") (pinfunction "DAT1_8") (pintype "bidirectional"))
    )
    (net (code "173") (name "unconnected-(U$3-DAT2-Pad9)") (class "Default")
      (node (ref "U$3") (pin "9") (pinfunction "DAT2_9") (pintype "bidirectional"))
    )
    (net (code "174") (name "unconnected-(U$3-WRITE_PROTECT-PadWP)") (class "Default")
      (node (ref "U$3") (pin "WP") (pinfunction "WRITE_PROTECT_WP") (pintype "passive"))
    )
    (net (code "175") (name "unconnected-(U$4-VOUT2-Pad2)") (class "Default")
      (node (ref "U$4") (pin "2") (pinfunction "VOUT2_2") (pintype "bidirectional"))
    )
    (net (code "176") (name "unconnected-(U1N-HSWAP_EN-PadP142)") (class "Default")
      (node (ref "U1") (pin "P142") (pinfunction "HSWAP_EN_P142") (pintype "bidirectional"))
    )
    (net (code "177") (name "unconnected-(X1-Pad10)") (class "Default")
      (node (ref "X1") (pin "10") (pinfunction "10_10") (pintype "passive"))
    )
    (net (code "178") (name "unconnected-(X1-Pad12)") (class "Default")
      (node (ref "X1") (pin "12") (pinfunction "12_12") (pintype "passive"))
    )
    (net (code "179") (name "unconnected-(X3-Pad2)") (class "Default")
      (node (ref "X3") (pin "2") (pinfunction "2_2") (pintype "passive"))
    )
    (net (code "180") (name "unconnected-(X3-Pad8)") (class "Default")
      (node (ref "X3") (pin "8") (pinfunction "8_8") (pintype "passive"))
    )
    (net (code "181") (name "unconnected-(X4-PadG2)") (class "Default")
      (node (ref "X4") (pin "G2") (pinfunction "G2_G2") (pintype "passive"))
    )
    (net (code "182") (name "unconnected-(X5-PadG2)") (class "Default")
      (node (ref "X5") (pin "G2") (pinfunction "G2_G2") (pintype "passive"))
    )
    (net (code "183") (name "unconnected-(X6-Pad1)") (class "Default")
      (node (ref "X6") (pin "1") (pinfunction "1_1") (pintype "passive"))
    )
  )
)
